# slice_v6_zp.net
KiCad netlist of a schematic drawn in EAGLE
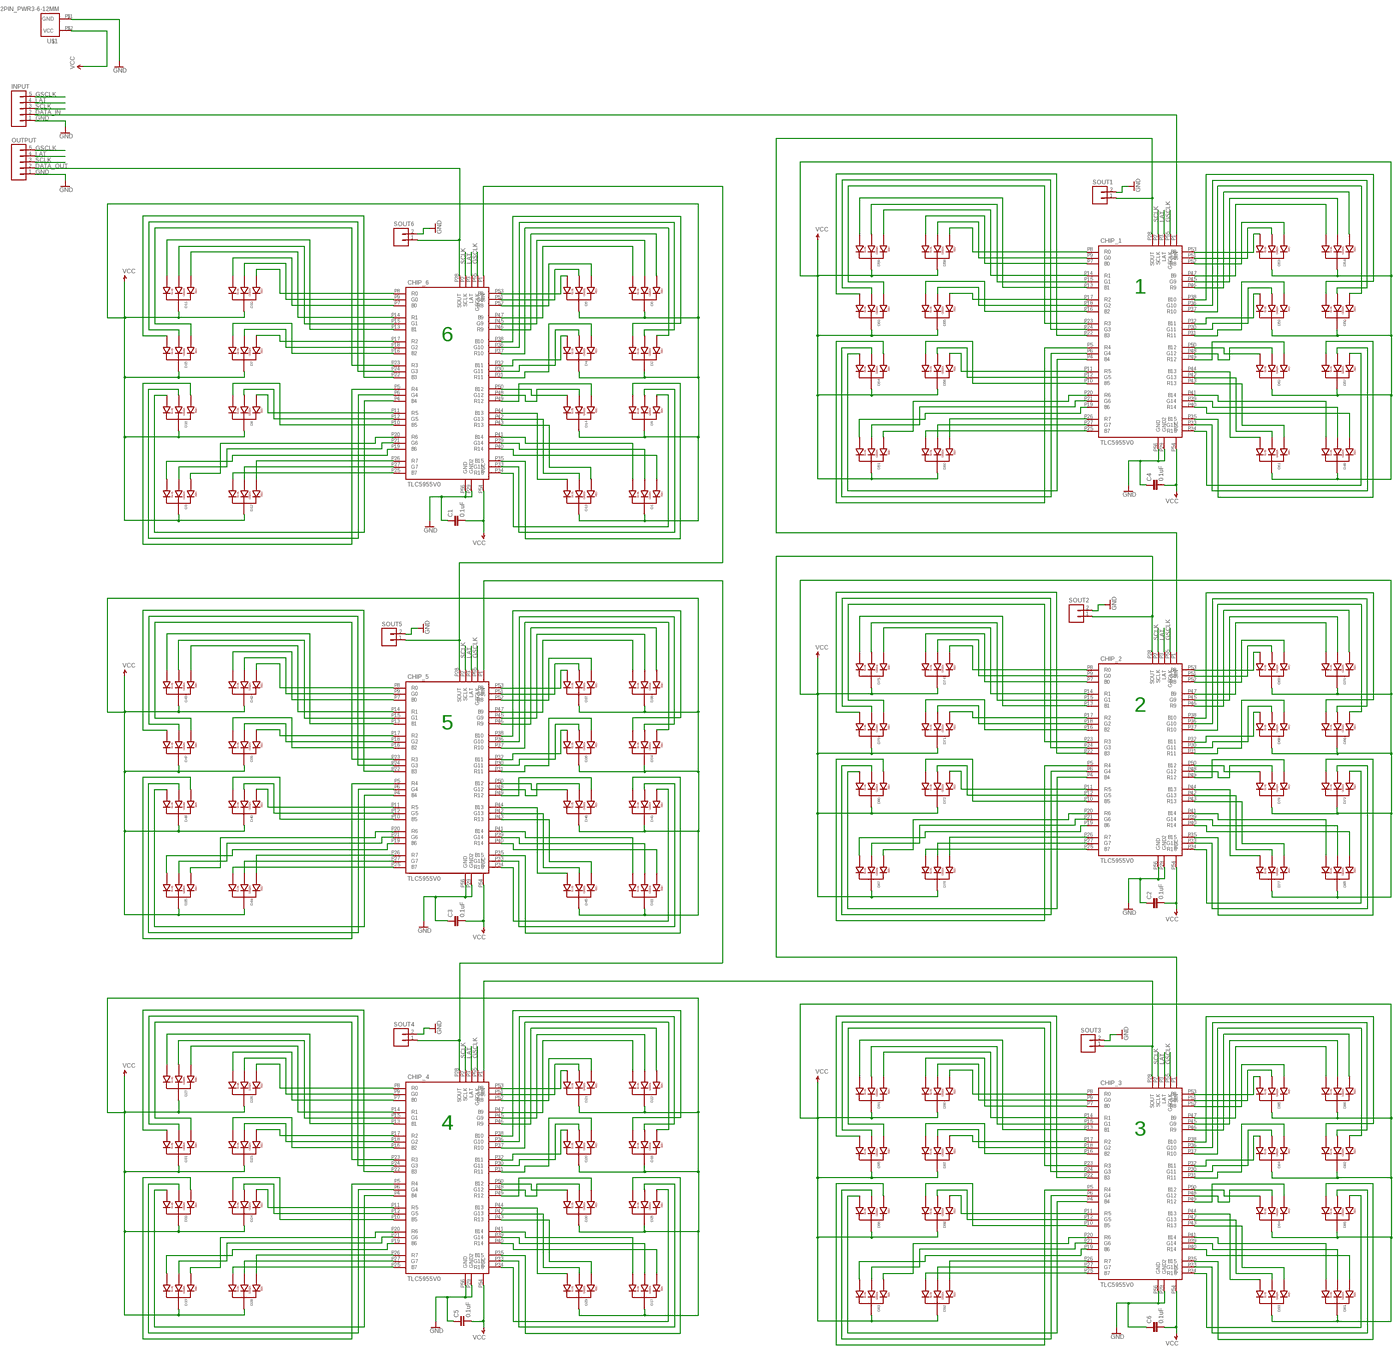
[diagram p0: schematic, sheet 1, overview]
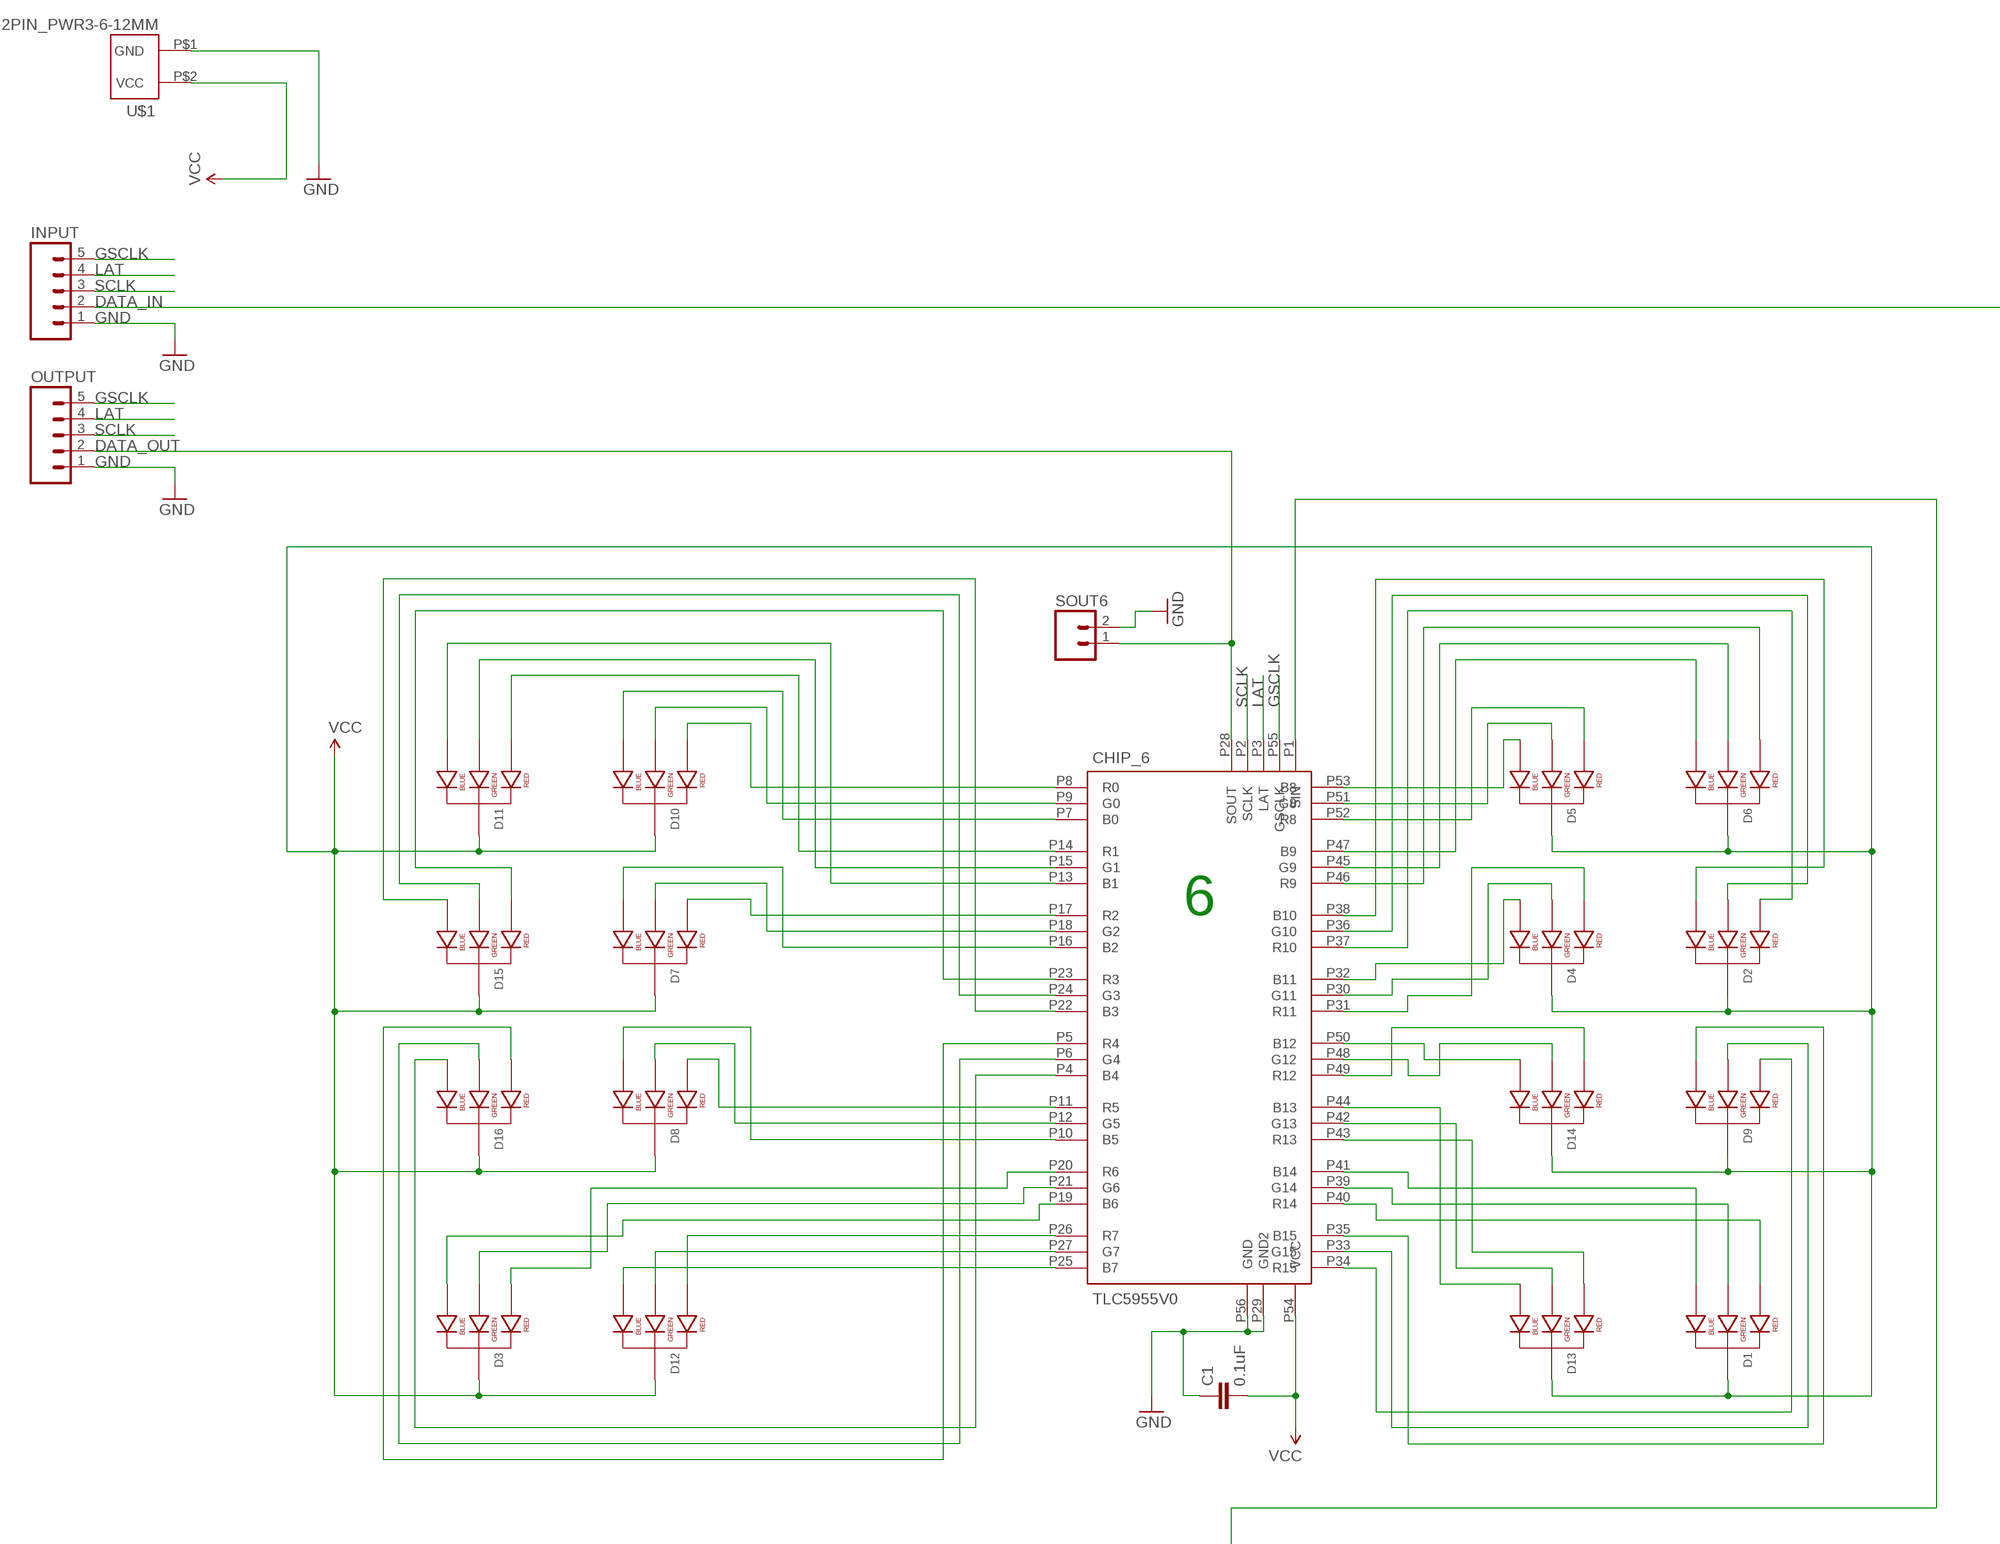
[diagram p1: schematic, sheet 1, part 1 of 4]
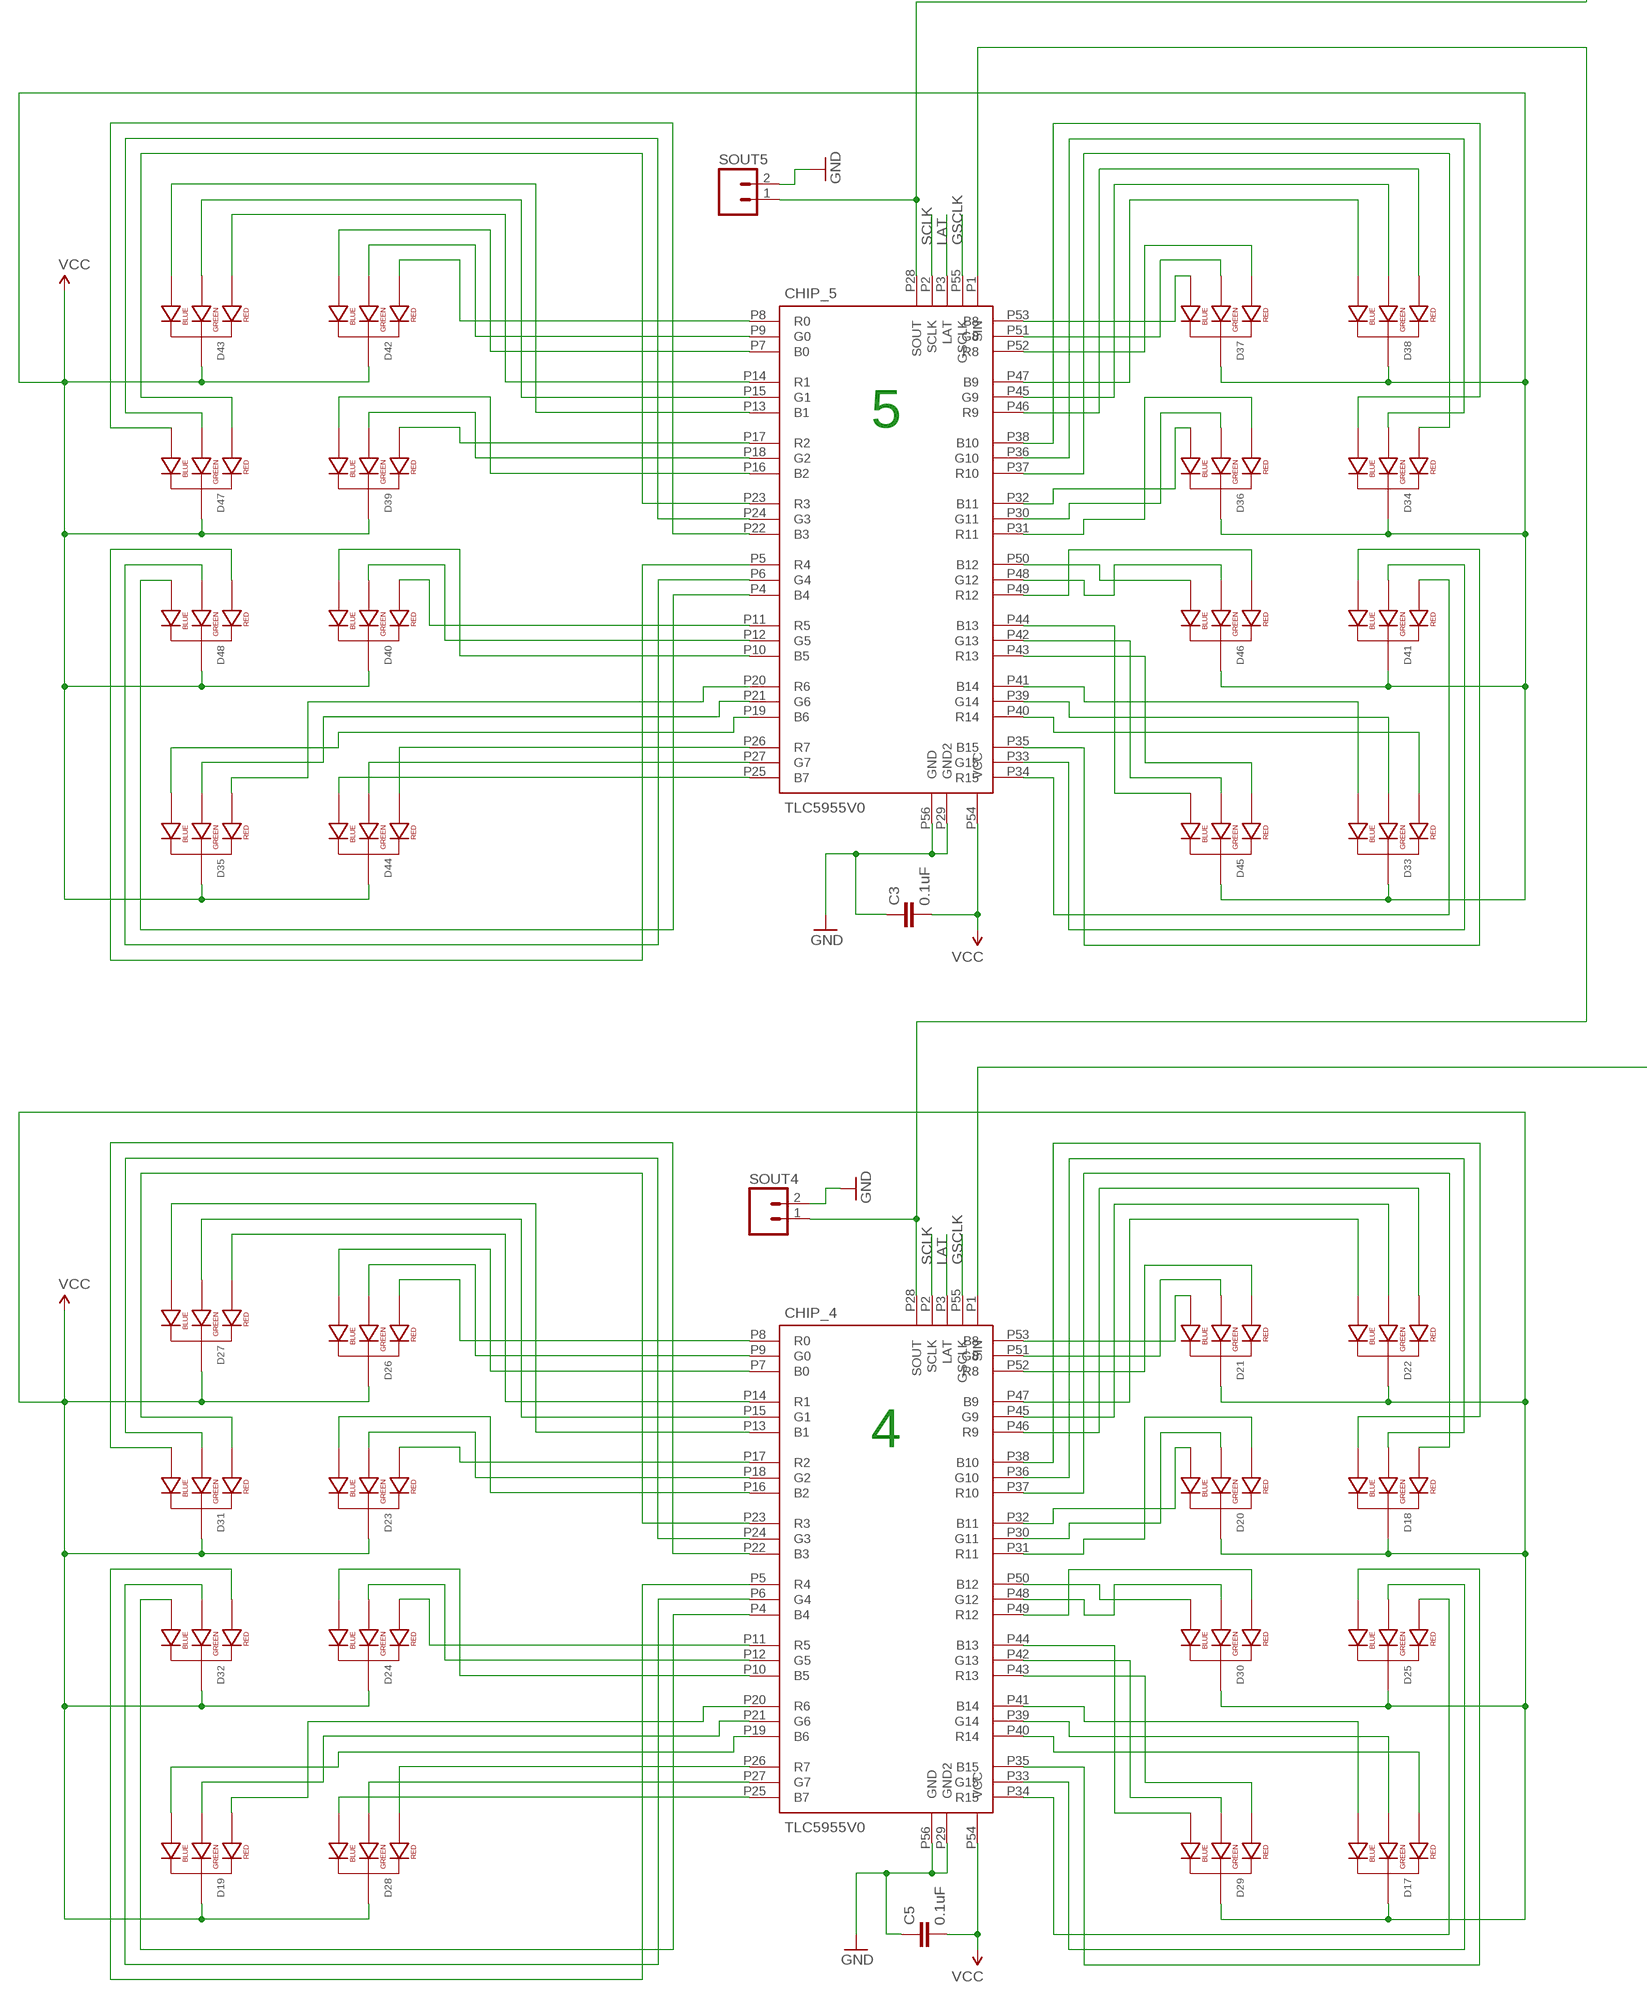
[diagram p2: schematic, sheet 1, part 2 of 4]
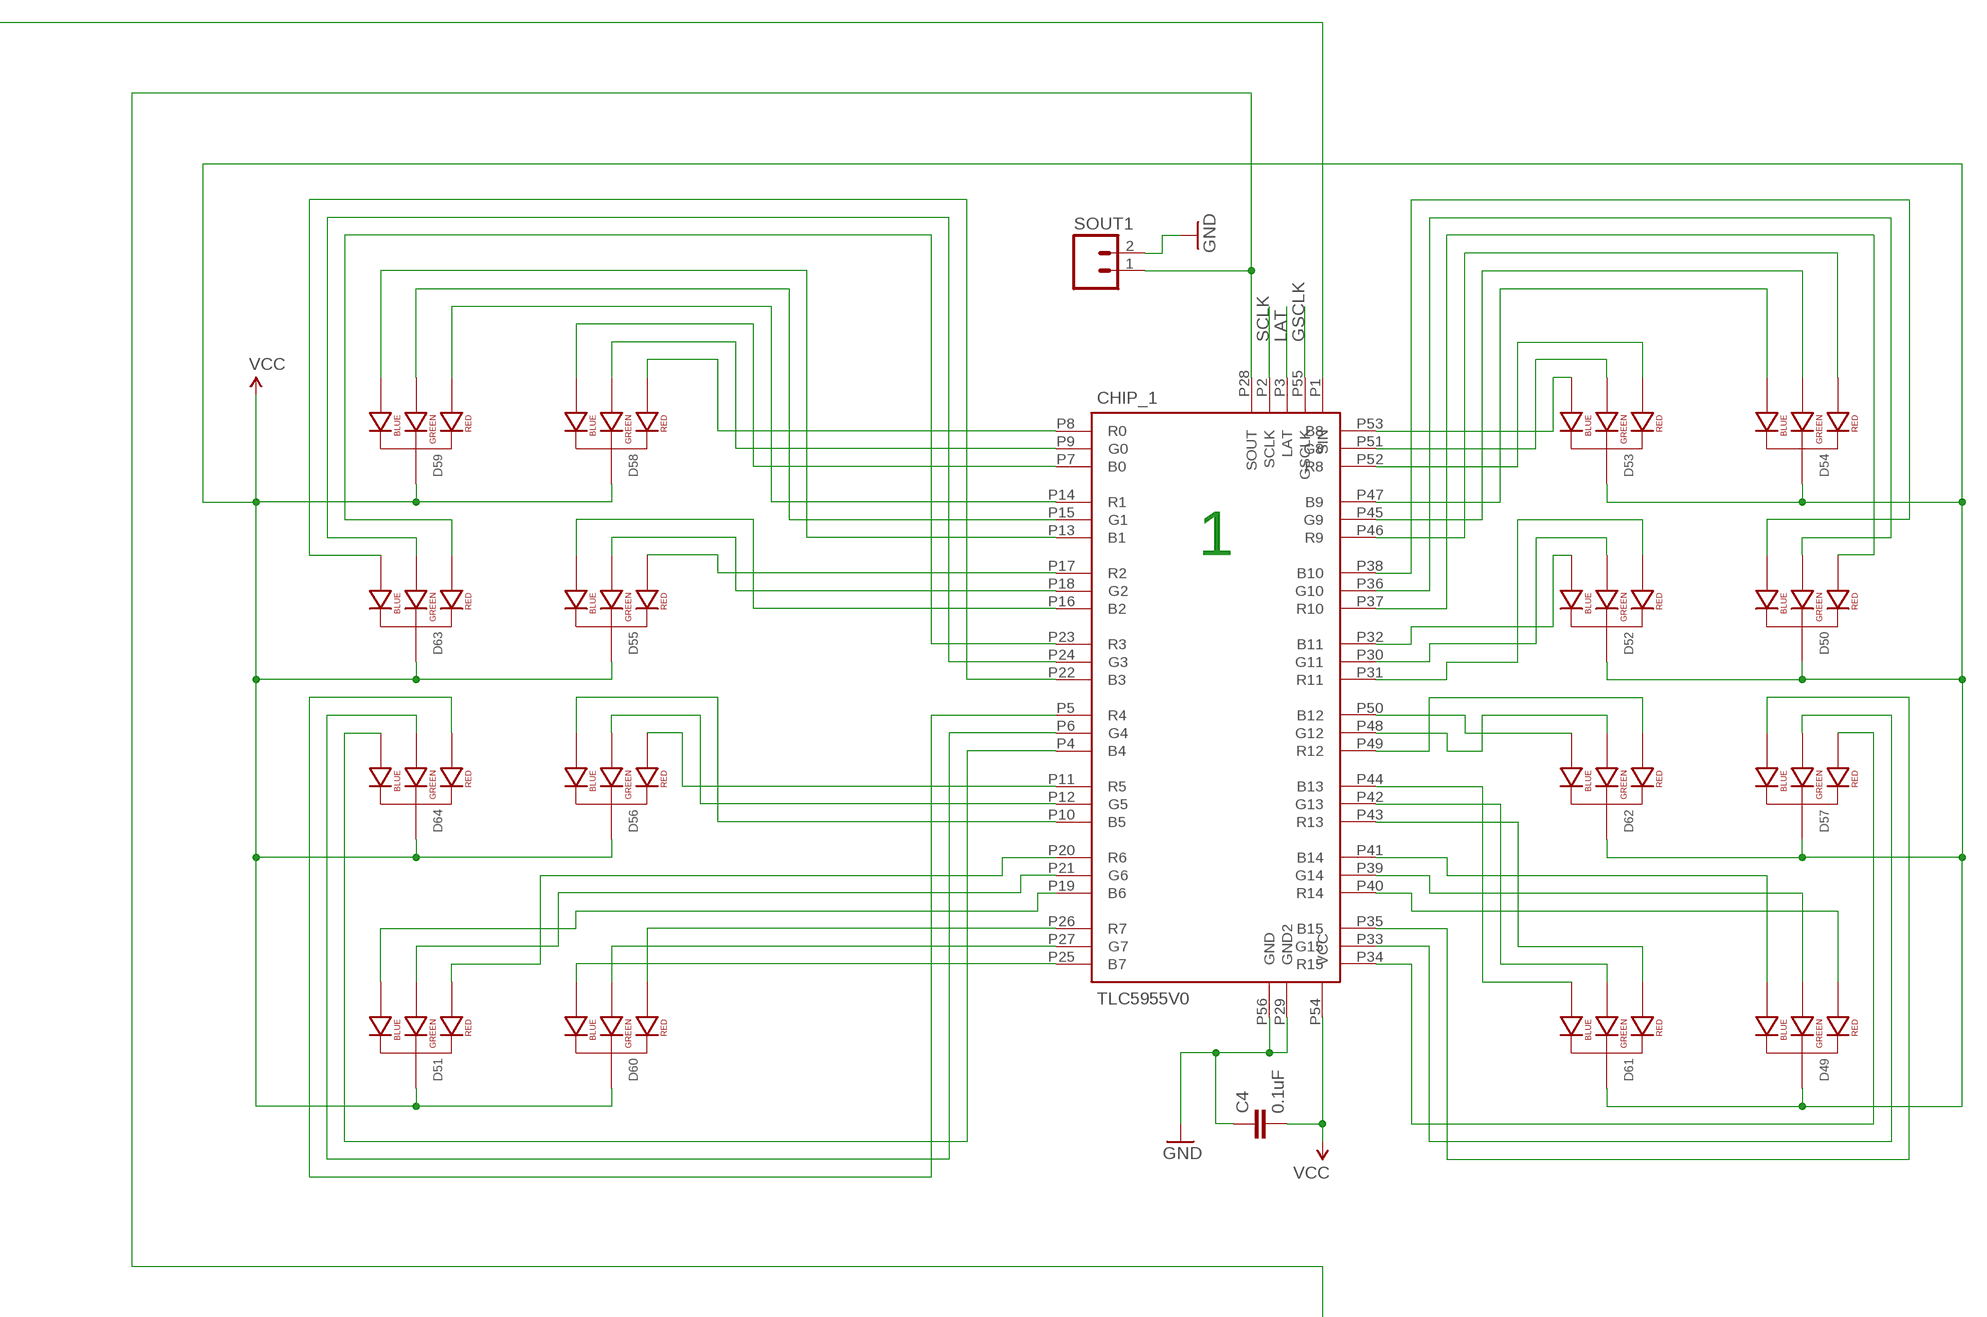
[diagram p3: schematic, sheet 1, part 3 of 4]
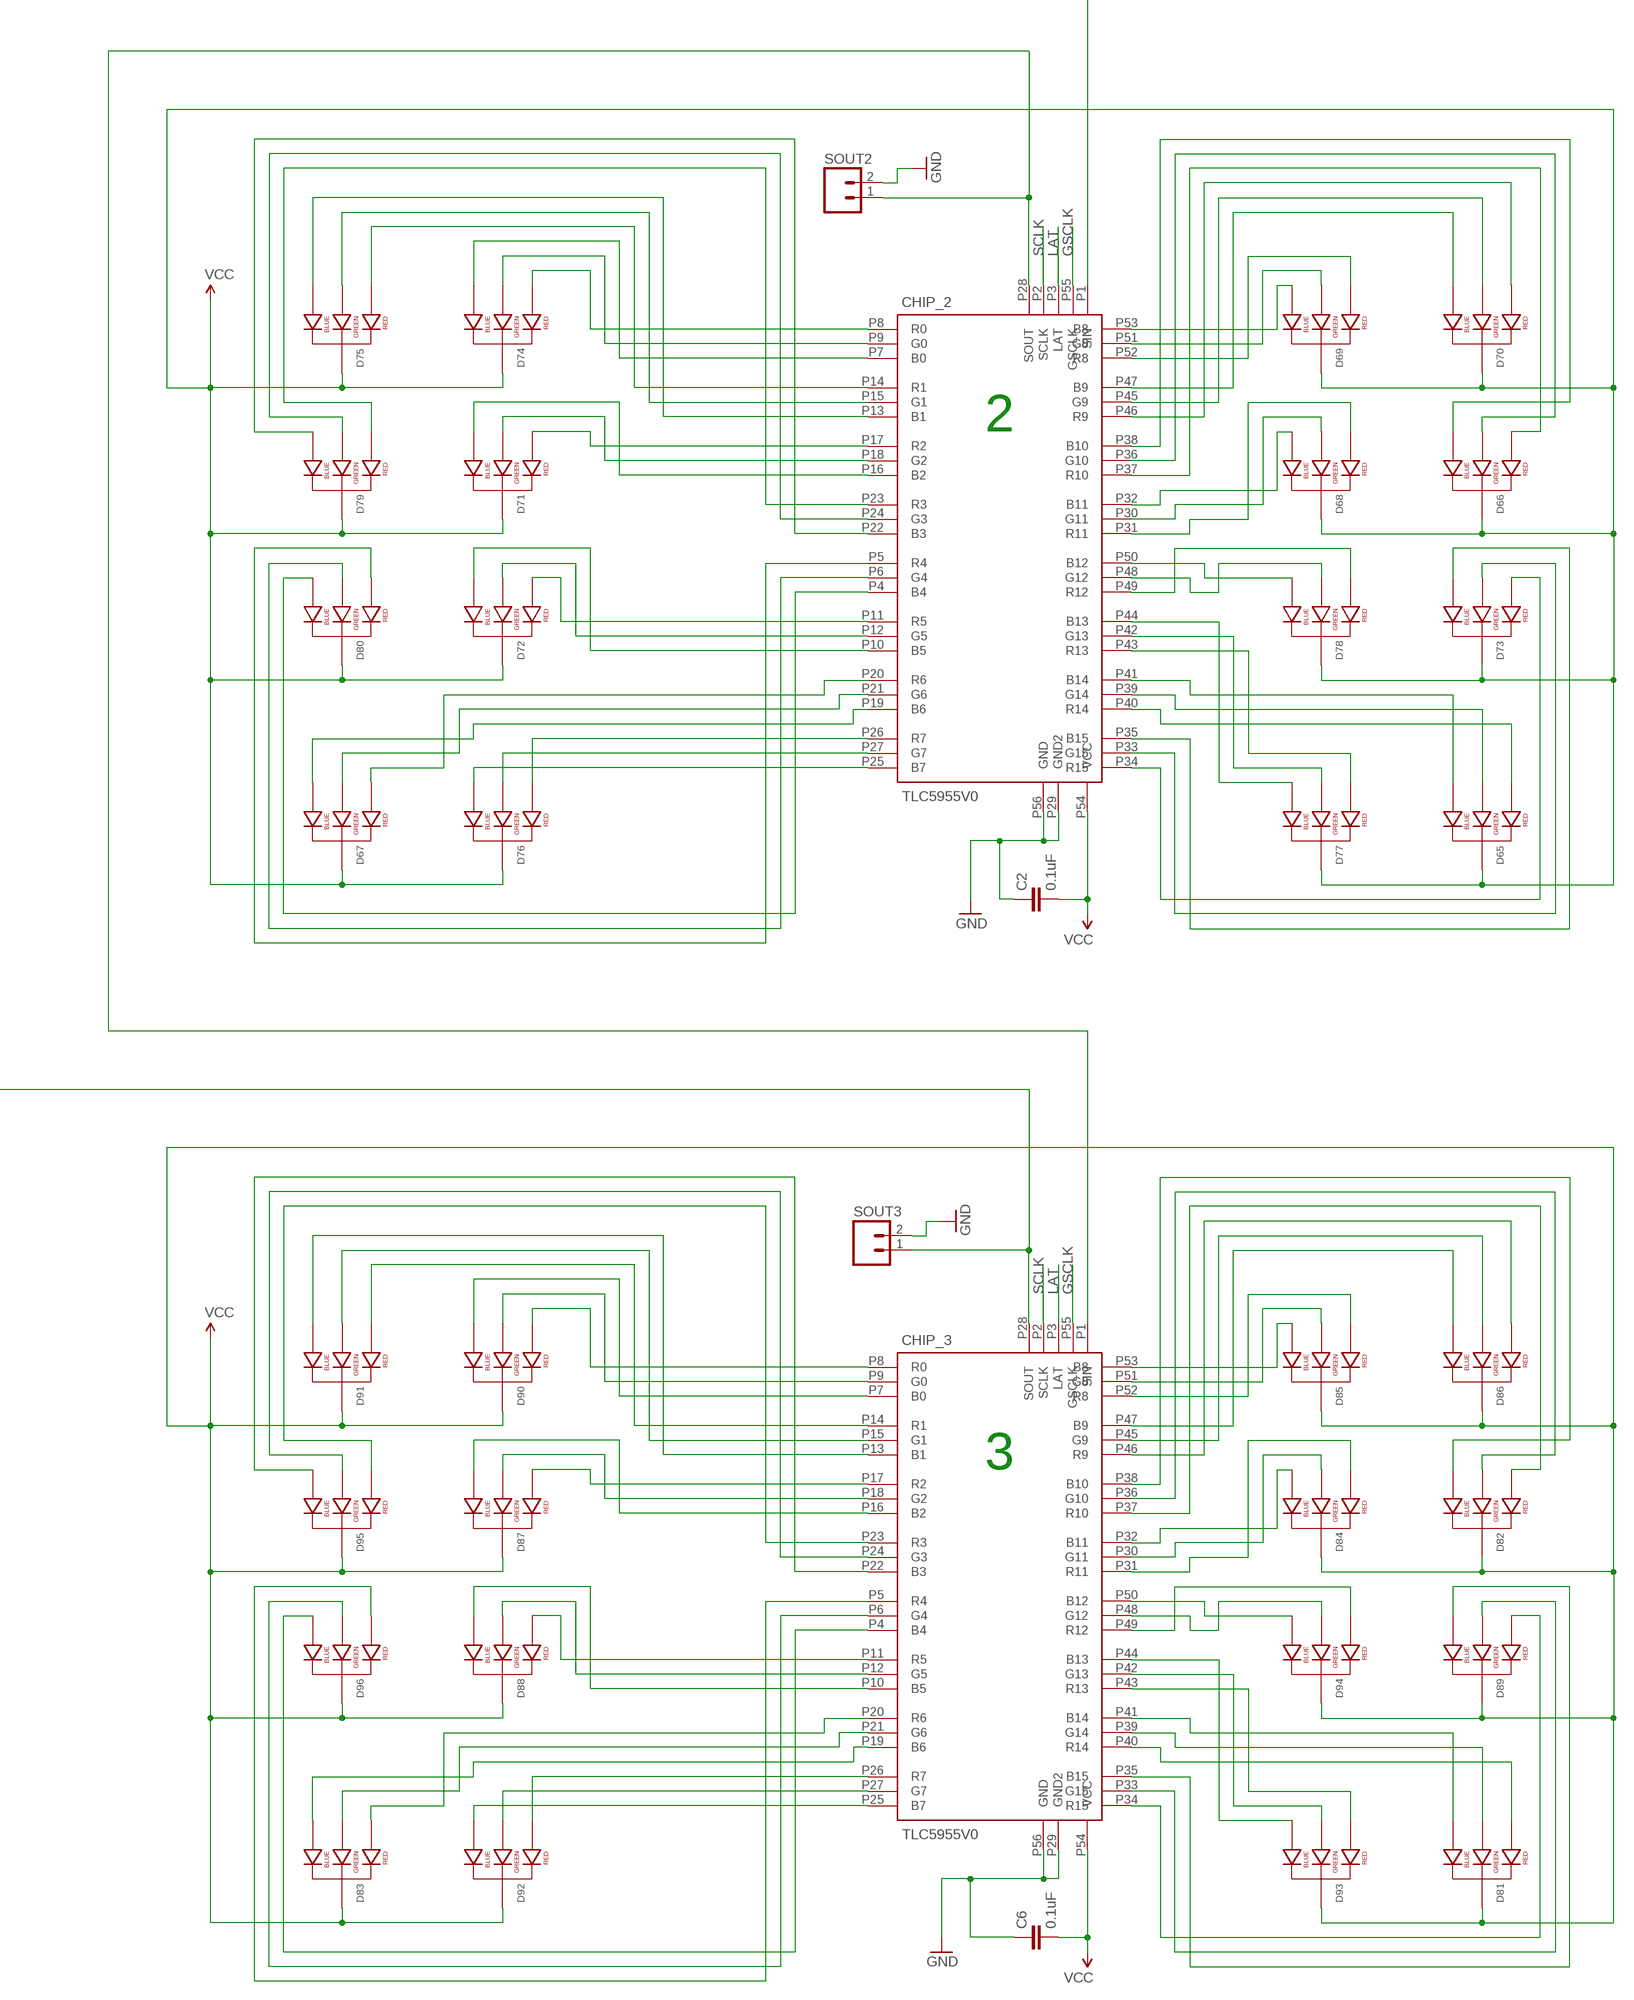
[diagram p4: schematic, sheet 1, part 4 of 4]

(export (version "E")
  (design (tool "Eeschema 10.0.6"))
  (components
    (comp (ref "C1")
      (value "0.1uF")
      (footprint "eagle-import:0603-CAP")
      (libsource (lib "eagle-import") (part "0.1UF-25V(+80/-20%)(0603)"))
    )
    (comp (ref "C2")
      (value "0.1uF")
      (footprint "eagle-import:0603-CAP")
      (libsource (lib "eagle-import") (part "0.1UF-25V(+80/-20%)(0603)"))
    )
    (comp (ref "C3")
      (value "0.1uF")
      (footprint "eagle-import:0603-CAP")
      (libsource (lib "eagle-import") (part "0.1UF-25V(+80/-20%)(0603)"))
    )
    (comp (ref "C4")
      (value "0.1uF")
      (footprint "eagle-import:0603-CAP")
      (libsource (lib "eagle-import") (part "0.1UF-25V(+80/-20%)(0603)"))
    )
    (comp (ref "C5")
      (value "0.1uF")
      (footprint "eagle-import:0603-CAP")
      (libsource (lib "eagle-import") (part "0.1UF-25V(+80/-20%)(0603)"))
    )
    (comp (ref "C6")
      (value "0.1uF")
      (footprint "eagle-import:0603-CAP")
      (libsource (lib "eagle-import") (part "0.1UF-25V(+80/-20%)(0603)"))
    )
    (comp (ref "CHIP_1")
      (value "TLC5955V0")
      (footprint "eagle-import:56-HTSSOP")
      (libsource (lib "eagle-import") (part "TLC5955V0"))
    )
    (comp (ref "CHIP_2")
      (value "TLC5955V0")
      (footprint "eagle-import:56-HTSSOP")
      (libsource (lib "eagle-import") (part "TLC5955V0"))
    )
    (comp (ref "CHIP_3")
      (value "TLC5955V0")
      (footprint "eagle-import:56-HTSSOP")
      (libsource (lib "eagle-import") (part "TLC5955V0"))
    )
    (comp (ref "CHIP_4")
      (value "TLC5955V0")
      (footprint "eagle-import:56-HTSSOP")
      (libsource (lib "eagle-import") (part "TLC5955V0"))
    )
    (comp (ref "CHIP_5")
      (value "TLC5955V0")
      (footprint "eagle-import:56-HTSSOP")
      (libsource (lib "eagle-import") (part "TLC5955V0"))
    )
    (comp (ref "CHIP_6")
      (value "TLC5955V0")
      (footprint "eagle-import:56-HTSSOP")
      (libsource (lib "eagle-import") (part "TLC5955V0"))
    )
    (comp (ref "D1")
      (value "LED-RGB-CC-THRUCLEAR")
      (footprint "eagle-import:LED-RGB-THRU")
      (libsource (lib "eagle-import") (part "LED-RGB-CC-THRUCLEAR"))
    )
    (comp (ref "D2")
      (value "LED-RGB-CC-THRUCLEAR")
      (footprint "eagle-import:LED-RGB-THRU")
      (libsource (lib "eagle-import") (part "LED-RGB-CC-THRUCLEAR"))
    )
    (comp (ref "D3")
      (value "LED-RGB-CC-THRUCLEAR")
      (footprint "eagle-import:LED-RGB-THRU")
      (libsource (lib "eagle-import") (part "LED-RGB-CC-THRUCLEAR"))
    )
    (comp (ref "D4")
      (value "LED-RGB-CC-THRUCLEAR")
      (footprint "eagle-import:LED-RGB-THRU")
      (libsource (lib "eagle-import") (part "LED-RGB-CC-THRUCLEAR"))
    )
    (comp (ref "D5")
      (value "LED-RGB-CC-THRUCLEAR")
      (footprint "eagle-import:LED-RGB-THRU")
      (libsource (lib "eagle-import") (part "LED-RGB-CC-THRUCLEAR"))
    )
    (comp (ref "D6")
      (value "LED-RGB-CC-THRUCLEAR")
      (footprint "eagle-import:LED-RGB-THRU")
      (libsource (lib "eagle-import") (part "LED-RGB-CC-THRUCLEAR"))
    )
    (comp (ref "D7")
      (value "LED-RGB-CC-THRUCLEAR")
      (footprint "eagle-import:LED-RGB-THRU")
      (libsource (lib "eagle-import") (part "LED-RGB-CC-THRUCLEAR"))
    )
    (comp (ref "D8")
      (value "LED-RGB-CC-THRUCLEAR")
      (footprint "eagle-import:LED-RGB-THRU")
      (libsource (lib "eagle-import") (part "LED-RGB-CC-THRUCLEAR"))
    )
    (comp (ref "D9")
      (value "LED-RGB-CC-THRUCLEAR")
      (footprint "eagle-import:LED-RGB-THRU")
      (libsource (lib "eagle-import") (part "LED-RGB-CC-THRUCLEAR"))
    )
    (comp (ref "D10")
      (value "LED-RGB-CC-THRUCLEAR")
      (footprint "eagle-import:LED-RGB-THRU")
      (libsource (lib "eagle-import") (part "LED-RGB-CC-THRUCLEAR"))
    )
    (comp (ref "D11")
      (value "LED-RGB-CC-THRUDIFFUSE")
      (footprint "eagle-import:LED-RGB-THRU")
      (libsource (lib "eagle-import") (part "LED-RGB-CC-THRUCLEAR"))
    )
    (comp (ref "D12")
      (value "LED-RGB-CC-THRUCLEAR")
      (footprint "eagle-import:LED-RGB-THRU")
      (libsource (lib "eagle-import") (part "LED-RGB-CC-THRUCLEAR"))
    )
    (comp (ref "D13")
      (value "LED-RGB-CC-THRUCLEAR")
      (footprint "eagle-import:LED-RGB-THRU")
      (libsource (lib "eagle-import") (part "LED-RGB-CC-THRUCLEAR"))
    )
    (comp (ref "D14")
      (value "LED-RGB-CC-THRUCLEAR")
      (footprint "eagle-import:LED-RGB-THRU")
      (libsource (lib "eagle-import") (part "LED-RGB-CC-THRUCLEAR"))
    )
    (comp (ref "D15")
      (value "LED-RGB-CC-THRUCLEAR")
      (footprint "eagle-import:LED-RGB-THRU")
      (libsource (lib "eagle-import") (part "LED-RGB-CC-THRUCLEAR"))
    )
    (comp (ref "D16")
      (value "LED-RGB-CC-THRUCLEAR")
      (footprint "eagle-import:LED-RGB-THRU")
      (libsource (lib "eagle-import") (part "LED-RGB-CC-THRUCLEAR"))
    )
    (comp (ref "D17")
      (value "LED-RGB-CC-THRUCLEAR")
      (footprint "eagle-import:LED-RGB-THRU")
      (libsource (lib "eagle-import") (part "LED-RGB-CC-THRUCLEAR"))
    )
    (comp (ref "D18")
      (value "LED-RGB-CC-THRUCLEAR")
      (footprint "eagle-import:LED-RGB-THRU")
      (libsource (lib "eagle-import") (part "LED-RGB-CC-THRUCLEAR"))
    )
    (comp (ref "D19")
      (value "LED-RGB-CC-THRUCLEAR")
      (footprint "eagle-import:LED-RGB-THRU")
      (libsource (lib "eagle-import") (part "LED-RGB-CC-THRUCLEAR"))
    )
    (comp (ref "D20")
      (value "LED-RGB-CC-THRUCLEAR")
      (footprint "eagle-import:LED-RGB-THRU")
      (libsource (lib "eagle-import") (part "LED-RGB-CC-THRUCLEAR"))
    )
    (comp (ref "D21")
      (value "LED-RGB-CC-THRUCLEAR")
      (footprint "eagle-import:LED-RGB-THRU")
      (libsource (lib "eagle-import") (part "LED-RGB-CC-THRUCLEAR"))
    )
    (comp (ref "D22")
      (value "LED-RGB-CC-THRUCLEAR")
      (footprint "eagle-import:LED-RGB-THRU")
      (libsource (lib "eagle-import") (part "LED-RGB-CC-THRUCLEAR"))
    )
    (comp (ref "D23")
      (value "LED-RGB-CC-THRUCLEAR")
      (footprint "eagle-import:LED-RGB-THRU")
      (libsource (lib "eagle-import") (part "LED-RGB-CC-THRUCLEAR"))
    )
    (comp (ref "D24")
      (value "LED-RGB-CC-THRUCLEAR")
      (footprint "eagle-import:LED-RGB-THRU")
      (libsource (lib "eagle-import") (part "LED-RGB-CC-THRUCLEAR"))
    )
    (comp (ref "D25")
      (value "LED-RGB-CC-THRUCLEAR")
      (footprint "eagle-import:LED-RGB-THRU")
      (libsource (lib "eagle-import") (part "LED-RGB-CC-THRUCLEAR"))
    )
    (comp (ref "D26")
      (value "LED-RGB-CC-THRUCLEAR")
      (footprint "eagle-import:LED-RGB-THRU")
      (libsource (lib "eagle-import") (part "LED-RGB-CC-THRUCLEAR"))
    )
    (comp (ref "D27")
      (value "LED-RGB-CC-THRUCLEAR")
      (footprint "eagle-import:LED-RGB-THRU")
      (libsource (lib "eagle-import") (part "LED-RGB-CC-THRUCLEAR"))
    )
    (comp (ref "D28")
      (value "LED-RGB-CC-THRUCLEAR")
      (footprint "eagle-import:LED-RGB-THRU")
      (libsource (lib "eagle-import") (part "LED-RGB-CC-THRUCLEAR"))
    )
    (comp (ref "D29")
      (value "LED-RGB-CC-THRUCLEAR")
      (footprint "eagle-import:LED-RGB-THRU")
      (libsource (lib "eagle-import") (part "LED-RGB-CC-THRUCLEAR"))
    )
    (comp (ref "D30")
      (value "LED-RGB-CC-THRUCLEAR")
      (footprint "eagle-import:LED-RGB-THRU")
      (libsource (lib "eagle-import") (part "LED-RGB-CC-THRUCLEAR"))
    )
    (comp (ref "D31")
      (value "LED-RGB-CC-THRUCLEAR")
      (footprint "eagle-import:LED-RGB-THRU")
      (libsource (lib "eagle-import") (part "LED-RGB-CC-THRUCLEAR"))
    )
    (comp (ref "D32")
      (value "LED-RGB-CC-THRUCLEAR")
      (footprint "eagle-import:LED-RGB-THRU")
      (libsource (lib "eagle-import") (part "LED-RGB-CC-THRUCLEAR"))
    )
    (comp (ref "D33")
      (value "LED-RGB-CC-THRUCLEAR")
      (footprint "eagle-import:LED-RGB-THRU")
      (libsource (lib "eagle-import") (part "LED-RGB-CC-THRUCLEAR"))
    )
    (comp (ref "D34")
      (value "LED-RGB-CC-THRUCLEAR")
      (footprint "eagle-import:LED-RGB-THRU")
      (libsource (lib "eagle-import") (part "LED-RGB-CC-THRUCLEAR"))
    )
    (comp (ref "D35")
      (value "1")
      (footprint "eagle-import:LED-RGB-THRU")
      (libsource (lib "eagle-import") (part "LED-RGB-CC-THRUCLEAR"))
    )
    (comp (ref "D36")
      (value "LED-RGB-CC-THRUCLEAR")
      (footprint "eagle-import:LED-RGB-THRU")
      (libsource (lib "eagle-import") (part "LED-RGB-CC-THRUCLEAR"))
    )
    (comp (ref "D37")
      (value "LED-RGB-CC-THRUCLEAR")
      (footprint "eagle-import:LED-RGB-THRU")
      (libsource (lib "eagle-import") (part "LED-RGB-CC-THRUCLEAR"))
    )
    (comp (ref "D38")
      (value "LED-RGB-CC-THRUCLEAR")
      (footprint "eagle-import:LED-RGB-THRU")
      (libsource (lib "eagle-import") (part "LED-RGB-CC-THRUCLEAR"))
    )
    (comp (ref "D39")
      (value "LED-RGB-CC-THRUCLEAR")
      (footprint "eagle-import:LED-RGB-THRU")
      (libsource (lib "eagle-import") (part "LED-RGB-CC-THRUCLEAR"))
    )
    (comp (ref "D40")
      (value "LED-RGB-CC-THRUCLEAR")
      (footprint "eagle-import:LED-RGB-THRU")
      (libsource (lib "eagle-import") (part "LED-RGB-CC-THRUCLEAR"))
    )
    (comp (ref "D41")
      (value "LED-RGB-CC-THRUCLEAR")
      (footprint "eagle-import:LED-RGB-THRU")
      (libsource (lib "eagle-import") (part "LED-RGB-CC-THRUCLEAR"))
    )
    (comp (ref "D42")
      (value "LED-RGB-CC-THRUCLEAR")
      (footprint "eagle-import:LED-RGB-THRU")
      (libsource (lib "eagle-import") (part "LED-RGB-CC-THRUCLEAR"))
    )
    (comp (ref "D43")
      (value "LED-RGB-CC-THRUCLEAR")
      (footprint "eagle-import:LED-RGB-THRU")
      (libsource (lib "eagle-import") (part "LED-RGB-CC-THRUCLEAR"))
    )
    (comp (ref "D44")
      (value "LED-RGB-CC-THRUCLEAR")
      (footprint "eagle-import:LED-RGB-THRU")
      (libsource (lib "eagle-import") (part "LED-RGB-CC-THRUCLEAR"))
    )
    (comp (ref "D45")
      (value "LED-RGB-CC-THRUCLEAR")
      (footprint "eagle-import:LED-RGB-THRU")
      (libsource (lib "eagle-import") (part "LED-RGB-CC-THRUCLEAR"))
    )
    (comp (ref "D46")
      (value "LED-RGB-CC-THRUCLEAR")
      (footprint "eagle-import:LED-RGB-THRU")
      (libsource (lib "eagle-import") (part "LED-RGB-CC-THRUCLEAR"))
    )
    (comp (ref "D47")
      (value "LED-RGB-CC-THRUCLEAR")
      (footprint "eagle-import:LED-RGB-THRU")
      (libsource (lib "eagle-import") (part "LED-RGB-CC-THRUCLEAR"))
    )
    (comp (ref "D48")
      (value "LED-RGB-CC-THRUCLEAR")
      (footprint "eagle-import:LED-RGB-THRU")
      (libsource (lib "eagle-import") (part "LED-RGB-CC-THRUCLEAR"))
    )
    (comp (ref "D49")
      (value "LED-RGB-CC-THRUCLEAR")
      (footprint "eagle-import:LED-RGB-THRU")
      (libsource (lib "eagle-import") (part "LED-RGB-CC-THRUCLEAR"))
    )
    (comp (ref "D50")
      (value "LED-RGB-CC-THRUCLEAR")
      (footprint "eagle-import:LED-RGB-THRU")
      (libsource (lib "eagle-import") (part "LED-RGB-CC-THRUCLEAR"))
    )
    (comp (ref "D51")
      (value "LED-RGB-CC-THRUCLEAR")
      (footprint "eagle-import:LED-RGB-THRU")
      (libsource (lib "eagle-import") (part "LED-RGB-CC-THRUCLEAR"))
    )
    (comp (ref "D52")
      (value "LED-RGB-CC-THRUCLEAR")
      (footprint "eagle-import:LED-RGB-THRU")
      (libsource (lib "eagle-import") (part "LED-RGB-CC-THRUCLEAR"))
    )
    (comp (ref "D53")
      (value "LED-RGB-CC-THRUCLEAR")
      (footprint "eagle-import:LED-RGB-THRU")
      (libsource (lib "eagle-import") (part "LED-RGB-CC-THRUCLEAR"))
    )
    (comp (ref "D54")
      (value "LED-RGB-CC-THRUCLEAR")
      (footprint "eagle-import:LED-RGB-THRU")
      (libsource (lib "eagle-import") (part "LED-RGB-CC-THRUCLEAR"))
    )
    (comp (ref "D55")
      (value "LED-RGB-CC-THRUCLEAR")
      (footprint "eagle-import:LED-RGB-THRU")
      (libsource (lib "eagle-import") (part "LED-RGB-CC-THRUCLEAR"))
    )
    (comp (ref "D56")
      (value "LED-RGB-CC-THRUCLEAR")
      (footprint "eagle-import:LED-RGB-THRU")
      (libsource (lib "eagle-import") (part "LED-RGB-CC-THRUCLEAR"))
    )
    (comp (ref "D57")
      (value "LED-RGB-CC-THRUCLEAR")
      (footprint "eagle-import:LED-RGB-THRU")
      (libsource (lib "eagle-import") (part "LED-RGB-CC-THRUCLEAR"))
    )
    (comp (ref "D58")
      (value "LED-RGB-CC-THRUCLEAR")
      (footprint "eagle-import:LED-RGB-THRU")
      (libsource (lib "eagle-import") (part "LED-RGB-CC-THRUCLEAR"))
    )
    (comp (ref "D59")
      (value "LED-RGB-CC-THRUCLEAR")
      (footprint "eagle-import:LED-RGB-THRU")
      (libsource (lib "eagle-import") (part "LED-RGB-CC-THRUCLEAR"))
    )
    (comp (ref "D60")
      (value "LED-RGB-CC-THRUCLEAR")
      (footprint "eagle-import:LED-RGB-THRU")
      (libsource (lib "eagle-import") (part "LED-RGB-CC-THRUCLEAR"))
    )
    (comp (ref "D61")
      (value "LED-RGB-CC-THRUCLEAR")
      (footprint "eagle-import:LED-RGB-THRU")
      (libsource (lib "eagle-import") (part "LED-RGB-CC-THRUCLEAR"))
    )
    (comp (ref "D62")
      (value "LED-RGB-CC-THRUCLEAR")
      (footprint "eagle-import:LED-RGB-THRU")
      (libsource (lib "eagle-import") (part "LED-RGB-CC-THRUCLEAR"))
    )
    (comp (ref "D63")
      (value "LED-RGB-CC-THRUCLEAR")
      (footprint "eagle-import:LED-RGB-THRU")
      (libsource (lib "eagle-import") (part "LED-RGB-CC-THRUCLEAR"))
    )
    (comp (ref "D64")
      (value "LED-RGB-CC-THRUCLEAR")
      (footprint "eagle-import:LED-RGB-THRU")
      (libsource (lib "eagle-import") (part "LED-RGB-CC-THRUCLEAR"))
    )
    (comp (ref "D65")
      (value "LED-RGB-CC-THRUCLEAR")
      (footprint "eagle-import:LED-RGB-THRU")
      (libsource (lib "eagle-import") (part "LED-RGB-CC-THRUCLEAR"))
    )
    (comp (ref "D66")
      (value "LED-RGB-CC-THRUCLEAR")
      (footprint "eagle-import:LED-RGB-THRU")
      (libsource (lib "eagle-import") (part "LED-RGB-CC-THRUCLEAR"))
    )
    (comp (ref "D67")
      (value "LED-RGB-CC-THRUCLEAR")
      (footprint "eagle-import:LED-RGB-THRU")
      (libsource (lib "eagle-import") (part "LED-RGB-CC-THRUCLEAR"))
    )
    (comp (ref "D68")
      (value "LED-RGB-CC-THRUCLEAR")
      (footprint "eagle-import:LED-RGB-THRU")
      (libsource (lib "eagle-import") (part "LED-RGB-CC-THRUCLEAR"))
    )
    (comp (ref "D69")
      (value "LED-RGB-CC-THRUCLEAR")
      (footprint "eagle-import:LED-RGB-THRU")
      (libsource (lib "eagle-import") (part "LED-RGB-CC-THRUCLEAR"))
    )
    (comp (ref "D70")
      (value "LED-RGB-CC-THRUCLEAR")
      (footprint "eagle-import:LED-RGB-THRU")
      (libsource (lib "eagle-import") (part "LED-RGB-CC-THRUCLEAR"))
    )
    (comp (ref "D71")
      (value "LED-RGB-CC-THRUCLEAR")
      (footprint "eagle-import:LED-RGB-THRU")
      (libsource (lib "eagle-import") (part "LED-RGB-CC-THRUCLEAR"))
    )
    (comp (ref "D72")
      (value "LED-RGB-CC-THRUCLEAR")
      (footprint "eagle-import:LED-RGB-THRU")
      (libsource (lib "eagle-import") (part "LED-RGB-CC-THRUCLEAR"))
    )
    (comp (ref "D73")
      (value "LED-RGB-CC-THRUCLEAR")
      (footprint "eagle-import:LED-RGB-THRU")
      (libsource (lib "eagle-import") (part "LED-RGB-CC-THRUCLEAR"))
    )
    (comp (ref "D74")
      (value "LED-RGB-CC-THRUCLEAR")
      (footprint "eagle-import:LED-RGB-THRU")
      (libsource (lib "eagle-import") (part "LED-RGB-CC-THRUCLEAR"))
    )
    (comp (ref "D75")
      (value "LED-RGB-CC-THRUCLEAR")
      (footprint "eagle-import:LED-RGB-THRU")
      (libsource (lib "eagle-import") (part "LED-RGB-CC-THRUCLEAR"))
    )
    (comp (ref "D76")
      (value "LED-RGB-CC-THRUCLEAR")
      (footprint "eagle-import:LED-RGB-THRU")
      (libsource (lib "eagle-import") (part "LED-RGB-CC-THRUCLEAR"))
    )
    (comp (ref "D77")
      (value "LED-RGB-CC-THRUCLEAR")
      (footprint "eagle-import:LED-RGB-THRU")
      (libsource (lib "eagle-import") (part "LED-RGB-CC-THRUCLEAR"))
    )
    (comp (ref "D78")
      (value "LED-RGB-CC-THRUCLEAR")
      (footprint "eagle-import:LED-RGB-THRU")
      (libsource (lib "eagle-import") (part "LED-RGB-CC-THRUCLEAR"))
    )
    (comp (ref "D79")
      (value "LED-RGB-CC-THRUCLEAR")
      (footprint "eagle-import:LED-RGB-THRU")
      (libsource (lib "eagle-import") (part "LED-RGB-CC-THRUCLEAR"))
    )
    (comp (ref "D80")
      (value "LED-RGB-CC-THRUCLEAR")
      (footprint "eagle-import:LED-RGB-THRU")
      (libsource (lib "eagle-import") (part "LED-RGB-CC-THRUCLEAR"))
    )
    (comp (ref "D81")
      (value "LED-RGB-CC-THRUCLEAR")
      (footprint "eagle-import:LED-RGB-THRU")
      (libsource (lib "eagle-import") (part "LED-RGB-CC-THRUCLEAR"))
    )
    (comp (ref "D82")
      (value "LED-RGB-CC-THRUCLEAR")
      (footprint "eagle-import:LED-RGB-THRU")
      (libsource (lib "eagle-import") (part "LED-RGB-CC-THRUCLEAR"))
    )
    (comp (ref "D83")
      (value "LED-RGB-CC-THRUCLEAR")
      (footprint "eagle-import:LED-RGB-THRU")
      (libsource (lib "eagle-import") (part "LED-RGB-CC-THRUCLEAR"))
    )
    (comp (ref "D84")
      (value "LED-RGB-CC-THRUCLEAR")
      (footprint "eagle-import:LED-RGB-THRU")
      (libsource (lib "eagle-import") (part "LED-RGB-CC-THRUCLEAR"))
    )
    (comp (ref "D85")
      (value "LED-RGB-CC-THRUCLEAR")
      (footprint "eagle-import:LED-RGB-THRU")
      (libsource (lib "eagle-import") (part "LED-RGB-CC-THRUCLEAR"))
    )
    (comp (ref "D86")
      (value "LED-RGB-CC-THRUCLEAR")
      (footprint "eagle-import:LED-RGB-THRU")
      (libsource (lib "eagle-import") (part "LED-RGB-CC-THRUCLEAR"))
    )
    (comp (ref "D87")
      (value "LED-RGB-CC-THRUCLEAR")
      (footprint "eagle-import:LED-RGB-THRU")
      (libsource (lib "eagle-import") (part "LED-RGB-CC-THRUCLEAR"))
    )
    (comp (ref "D88")
      (value "LED-RGB-CC-THRUCLEAR")
      (footprint "eagle-import:LED-RGB-THRU")
      (libsource (lib "eagle-import") (part "LED-RGB-CC-THRUCLEAR"))
    )
    (comp (ref "D89")
      (value "LED-RGB-CC-THRUCLEAR")
      (footprint "eagle-import:LED-RGB-THRU")
      (libsource (lib "eagle-import") (part "LED-RGB-CC-THRUCLEAR"))
    )
    (comp (ref "D90")
      (value "LED-RGB-CC-THRUCLEAR")
      (footprint "eagle-import:LED-RGB-THRU")
      (libsource (lib "eagle-import") (part "LED-RGB-CC-THRUCLEAR"))
    )
    (comp (ref "D91")
      (value "LED-RGB-CC-THRUCLEAR")
      (footprint "eagle-import:LED-RGB-THRU")
      (libsource (lib "eagle-import") (part "LED-RGB-CC-THRUCLEAR"))
    )
    (comp (ref "D92")
      (value "LED-RGB-CC-THRUCLEAR")
      (footprint "eagle-import:LED-RGB-THRU")
      (libsource (lib "eagle-import") (part "LED-RGB-CC-THRUCLEAR"))
    )
    (comp (ref "D93")
      (value "LED-RGB-CC-THRUCLEAR")
      (footprint "eagle-import:LED-RGB-THRU")
      (libsource (lib "eagle-import") (part "LED-RGB-CC-THRUCLEAR"))
    )
    (comp (ref "D94")
      (value "LED-RGB-CC-THRUCLEAR")
      (footprint "eagle-import:LED-RGB-THRU")
      (libsource (lib "eagle-import") (part "LED-RGB-CC-THRUCLEAR"))
    )
    (comp (ref "D95")
      (value "LED-RGB-CC-THRUCLEAR")
      (footprint "eagle-import:LED-RGB-THRU")
      (libsource (lib "eagle-import") (part "LED-RGB-CC-THRUCLEAR"))
    )
    (comp (ref "D96")
      (value "LED-RGB-CC-THRUCLEAR")
      (footprint "eagle-import:LED-RGB-THRU")
      (libsource (lib "eagle-import") (part "LED-RGB-CC-THRUCLEAR"))
    )
    (comp (ref "INPUT")
      (value "M05LOCK_LONGPADS")
      (footprint "eagle-import:1X05_LOCK_LONGPADS")
      (libsource (lib "eagle-import") (part "M05LOCK_LONGPADS"))
    )
    (comp (ref "OUTPUT")
      (value "M05LOCK_LONGPADS")
      (footprint "eagle-import:1X05_LOCK_LONGPADS")
      (libsource (lib "eagle-import") (part "M05LOCK_LONGPADS"))
    )
    (comp (ref "SOUT1")
      (value "M02LOCK")
      (footprint "eagle-import:1X02_LOCK")
      (libsource (lib "eagle-import") (part "M02LOCK"))
    )
    (comp (ref "SOUT2")
      (value "M02LOCK")
      (footprint "eagle-import:1X02_LOCK")
      (libsource (lib "eagle-import") (part "M02LOCK"))
    )
    (comp (ref "SOUT3")
      (value "M02LOCK")
      (footprint "eagle-import:1X02_LOCK")
      (libsource (lib "eagle-import") (part "M02LOCK"))
    )
    (comp (ref "SOUT4")
      (value "M02LOCK")
      (footprint "eagle-import:1X02_LOCK")
      (libsource (lib "eagle-import") (part "M02LOCK"))
    )
    (comp (ref "SOUT5")
      (value "M02LOCK")
      (footprint "eagle-import:1X02_LOCK")
      (libsource (lib "eagle-import") (part "M02LOCK"))
    )
    (comp (ref "SOUT6")
      (value "M02LOCK")
      (footprint "eagle-import:1X02_LOCK")
      (libsource (lib "eagle-import") (part "M02LOCK"))
    )
    (comp (ref "U$1")
      (value "2PIN_PWR3-6-12MM")
      (footprint "eagle-import:2PIN_HOLES_PWR")
      (libsource (lib "eagle-import") (part "2PIN_PWR3-6-12MM"))
    )
  )
  (nets
    (net (code "1") (name "/DATA_IN") (class "Default")
      (node (ref "CHIP_1") (pin "P1") (pinfunction "SIN_P1") (pintype "bidirectional"))
      (node (ref "INPUT") (pin "2") (pinfunction "2_2") (pintype "passive"))
    )
    (net (code "2") (name "/DATA_OUT") (class "Default")
      (node (ref "CHIP_6") (pin "P28") (pinfunction "SOUT_P28") (pintype "bidirectional"))
      (node (ref "OUTPUT") (pin "2") (pinfunction "2_2") (pintype "passive"))
      (node (ref "SOUT6") (pin "1") (pinfunction "1_1") (pintype "passive"))
    )
    (net (code "3") (name "/GSCLK") (class "Default")
      (node (ref "CHIP_1") (pin "P55") (pinfunction "GSCLK_P55") (pintype "bidirectional"))
      (node (ref "CHIP_2") (pin "P55") (pinfunction "GSCLK_P55") (pintype "bidirectional"))
      (node (ref "CHIP_3") (pin "P55") (pinfunction "GSCLK_P55") (pintype "bidirectional"))
      (node (ref "CHIP_4") (pin "P55") (pinfunction "GSCLK_P55") (pintype "bidirectional"))
      (node (ref "CHIP_5") (pin "P55") (pinfunction "GSCLK_P55") (pintype "bidirectional"))
      (node (ref "CHIP_6") (pin "P55") (pinfunction "GSCLK_P55") (pintype "bidirectional"))
      (node (ref "INPUT") (pin "5") (pinfunction "5_5") (pintype "passive"))
      (node (ref "OUTPUT") (pin "5") (pinfunction "5_5") (pintype "passive"))
    )
    (net (code "4") (name "/LAT") (class "Default")
      (node (ref "CHIP_1") (pin "P3") (pinfunction "LAT_P3") (pintype "bidirectional"))
      (node (ref "CHIP_2") (pin "P3") (pinfunction "LAT_P3") (pintype "bidirectional"))
      (node (ref "CHIP_3") (pin "P3") (pinfunction "LAT_P3") (pintype "bidirectional"))
      (node (ref "CHIP_4") (pin "P3") (pinfunction "LAT_P3") (pintype "bidirectional"))
      (node (ref "CHIP_5") (pin "P3") (pinfunction "LAT_P3") (pintype "bidirectional"))
      (node (ref "CHIP_6") (pin "P3") (pinfunction "LAT_P3") (pintype "bidirectional"))
      (node (ref "INPUT") (pin "4") (pinfunction "4_4") (pintype "passive"))
      (node (ref "OUTPUT") (pin "4") (pinfunction "4_4") (pintype "passive"))
    )
    (net (code "5") (name "/SCLK") (class "Default")
      (node (ref "CHIP_1") (pin "P2") (pinfunction "SCLK_P2") (pintype "bidirectional"))
      (node (ref "CHIP_2") (pin "P2") (pinfunction "SCLK_P2") (pintype "bidirectional"))
      (node (ref "CHIP_3") (pin "P2") (pinfunction "SCLK_P2") (pintype "bidirectional"))
      (node (ref "CHIP_4") (pin "P2") (pinfunction "SCLK_P2") (pintype "bidirectional"))
      (node (ref "CHIP_5") (pin "P2") (pinfunction "SCLK_P2") (pintype "bidirectional"))
      (node (ref "CHIP_6") (pin "P2") (pinfunction "SCLK_P2") (pintype "bidirectional"))
      (node (ref "INPUT") (pin "3") (pinfunction "3_3") (pintype "passive"))
      (node (ref "OUTPUT") (pin "3") (pinfunction "3_3") (pintype "passive"))
    )
    (net (code "6") (name "GND") (class "Default")
      (node (ref "C1") (pin "1") (pinfunction "1_1") (pintype "passive"))
      (node (ref "C2") (pin "1") (pinfunction "1_1") (pintype "passive"))
      (node (ref "C3") (pin "1") (pinfunction "1_1") (pintype "passive"))
      (node (ref "C4") (pin "1") (pinfunction "1_1") (pintype "passive"))
      (node (ref "C5") (pin "1") (pinfunction "1_1") (pintype "passive"))
      (node (ref "C6") (pin "1") (pinfunction "1_1") (pintype "passive"))
      (node (ref "CHIP_1") (pin "P29") (pinfunction "GND2_P29") (pintype "bidirectional"))
      (node (ref "CHIP_1") (pin "P56") (pinfunction "GND_P56") (pintype "bidirectional"))
      (node (ref "CHIP_2") (pin "P29") (pinfunction "GND2_P29") (pintype "bidirectional"))
      (node (ref "CHIP_2") (pin "P56") (pinfunction "GND_P56") (pintype "bidirectional"))
      (node (ref "CHIP_3") (pin "P29") (pinfunction "GND2_P29") (pintype "bidirectional"))
      (node (ref "CHIP_3") (pin "P56") (pinfunction "GND_P56") (pintype "bidirectional"))
      (node (ref "CHIP_4") (pin "P29") (pinfunction "GND2_P29") (pintype "bidirectional"))
      (node (ref "CHIP_4") (pin "P56") (pinfunction "GND_P56") (pintype "bidirectional"))
      (node (ref "CHIP_5") (pin "P29") (pinfunction "GND2_P29") (pintype "bidirectional"))
      (node (ref "CHIP_5") (pin "P56") (pinfunction "GND_P56") (pintype "bidirectional"))
      (node (ref "CHIP_6") (pin "P29") (pinfunction "GND2_P29") (pintype "bidirectional"))
      (node (ref "CHIP_6") (pin "P56") (pinfunction "GND_P56") (pintype "bidirectional"))
      (node (ref "INPUT") (pin "1") (pinfunction "1_1") (pintype "passive"))
      (node (ref "OUTPUT") (pin "1") (pinfunction "1_1") (pintype "passive"))
      (node (ref "SOUT1") (pin "2") (pinfunction "2_2") (pintype "passive"))
      (node (ref "SOUT2") (pin "2") (pinfunction "2_2") (pintype "passive"))
      (node (ref "SOUT3") (pin "2") (pinfunction "2_2") (pintype "passive"))
      (node (ref "SOUT4") (pin "2") (pinfunction "2_2") (pintype "passive"))
      (node (ref "SOUT5") (pin "2") (pinfunction "2_2") (pintype "passive"))
      (node (ref "SOUT6") (pin "2") (pinfunction "2_2") (pintype "passive"))
      (node (ref "U$1") (pin "P$1") (pinfunction "GND_P$1") (pintype "bidirectional"))
    )
    (net (code "7") (name "Net-(CHIP_1-B0)") (class "Default")
      (node (ref "CHIP_1") (pin "P7") (pinfunction "B0_P7") (pintype "bidirectional"))
      (node (ref "D58") (pin "4") (pinfunction "BLUE_CATHODE_4") (pintype "bidirectional"))
    )
    (net (code "8") (name "Net-(CHIP_1-B1)") (class "Default")
      (node (ref "CHIP_1") (pin "P13") (pinfunction "B1_P13") (pintype "bidirectional"))
      (node (ref "D59") (pin "4") (pinfunction "BLUE_CATHODE_4") (pintype "bidirectional"))
    )
    (net (code "9") (name "Net-(CHIP_1-B2)") (class "Default")
      (node (ref "CHIP_1") (pin "P16") (pinfunction "B2_P16") (pintype "bidirectional"))
      (node (ref "D55") (pin "4") (pinfunction "BLUE_CATHODE_4") (pintype "bidirectional"))
    )
    (net (code "10") (name "Net-(CHIP_1-B3)") (class "Default")
      (node (ref "CHIP_1") (pin "P22") (pinfunction "B3_P22") (pintype "bidirectional"))
      (node (ref "D63") (pin "4") (pinfunction "BLUE_CATHODE_4") (pintype "bidirectional"))
    )
    (net (code "11") (name "Net-(CHIP_1-B4)") (class "Default")
      (node (ref "CHIP_1") (pin "P4") (pinfunction "B4_P4") (pintype "bidirectional"))
      (node (ref "D64") (pin "4") (pinfunction "BLUE_CATHODE_4") (pintype "bidirectional"))
    )
    (net (code "12") (name "Net-(CHIP_1-B5)") (class "Default")
      (node (ref "CHIP_1") (pin "P10") (pinfunction "B5_P10") (pintype "bidirectional"))
      (node (ref "D56") (pin "4") (pinfunction "BLUE_CATHODE_4") (pintype "bidirectional"))
    )
    (net (code "13") (name "Net-(CHIP_1-B6)") (class "Default")
      (node (ref "CHIP_1") (pin "P19") (pinfunction "B6_P19") (pintype "bidirectional"))
      (node (ref "D51") (pin "4") (pinfunction "BLUE_CATHODE_4") (pintype "bidirectional"))
    )
    (net (code "14") (name "Net-(CHIP_1-B7)") (class "Default")
      (node (ref "CHIP_1") (pin "P25") (pinfunction "B7_P25") (pintype "bidirectional"))
      (node (ref "D60") (pin "4") (pinfunction "BLUE_CATHODE_4") (pintype "bidirectional"))
    )
    (net (code "15") (name "Net-(CHIP_1-B8)") (class "Default")
      (node (ref "CHIP_1") (pin "P53") (pinfunction "B8_P53") (pintype "bidirectional"))
      (node (ref "D53") (pin "4") (pinfunction "BLUE_CATHODE_4") (pintype "bidirectional"))
    )
    (net (code "16") (name "Net-(CHIP_1-B9)") (class "Default")
      (node (ref "CHIP_1") (pin "P47") (pinfunction "B9_P47") (pintype "bidirectional"))
      (node (ref "D54") (pin "4") (pinfunction "BLUE_CATHODE_4") (pintype "bidirectional"))
    )
    (net (code "17") (name "Net-(CHIP_1-B10)") (class "Default")
      (node (ref "CHIP_1") (pin "P38") (pinfunction "B10_P38") (pintype "bidirectional"))
      (node (ref "D50") (pin "4") (pinfunction "BLUE_CATHODE_4") (pintype "bidirectional"))
    )
    (net (code "18") (name "Net-(CHIP_1-B11)") (class "Default")
      (node (ref "CHIP_1") (pin "P32") (pinfunction "B11_P32") (pintype "bidirectional"))
      (node (ref "D52") (pin "4") (pinfunction "BLUE_CATHODE_4") (pintype "bidirectional"))
    )
    (net (code "19") (name "Net-(CHIP_1-B12)") (class "Default")
      (node (ref "CHIP_1") (pin "P50") (pinfunction "B12_P50") (pintype "bidirectional"))
      (node (ref "D62") (pin "4") (pinfunction "BLUE_CATHODE_4") (pintype "bidirectional"))
    )
    (net (code "20") (name "Net-(CHIP_1-B13)") (class "Default")
      (node (ref "CHIP_1") (pin "P44") (pinfunction "B13_P44") (pintype "bidirectional"))
      (node (ref "D61") (pin "4") (pinfunction "BLUE_CATHODE_4") (pintype "bidirectional"))
    )
    (net (code "21") (name "Net-(CHIP_1-B14)") (class "Default")
      (node (ref "CHIP_1") (pin "P41") (pinfunction "B14_P41") (pintype "bidirectional"))
      (node (ref "D49") (pin "4") (pinfunction "BLUE_CATHODE_4") (pintype "bidirectional"))
    )
    (net (code "22") (name "Net-(CHIP_1-B15)") (class "Default")
      (node (ref "CHIP_1") (pin "P35") (pinfunction "B15_P35") (pintype "bidirectional"))
      (node (ref "D57") (pin "4") (pinfunction "BLUE_CATHODE_4") (pintype "bidirectional"))
    )
    (net (code "23") (name "Net-(CHIP_1-G0)") (class "Default")
      (node (ref "CHIP_1") (pin "P9") (pinfunction "G0_P9") (pintype "bidirectional"))
      (node (ref "D58") (pin "1") (pinfunction "GREEN_CATHODE_1") (pintype "bidirectional"))
    )
    (net (code "24") (name "Net-(CHIP_1-G1)") (class "Default")
      (node (ref "CHIP_1") (pin "P15") (pinfunction "G1_P15") (pintype "bidirectional"))
      (node (ref "D59") (pin "1") (pinfunction "GREEN_CATHODE_1") (pintype "bidirectional"))
    )
    (net (code "25") (name "Net-(CHIP_1-G2)") (class "Default")
      (node (ref "CHIP_1") (pin "P18") (pinfunction "G2_P18") (pintype "bidirectional"))
      (node (ref "D55") (pin "1") (pinfunction "GREEN_CATHODE_1") (pintype "bidirectional"))
    )
    (net (code "26") (name "Net-(CHIP_1-G3)") (class "Default")
      (node (ref "CHIP_1") (pin "P24") (pinfunction "G3_P24") (pintype "bidirectional"))
      (node (ref "D63") (pin "1") (pinfunction "GREEN_CATHODE_1") (pintype "bidirectional"))
    )
    (net (code "27") (name "Net-(CHIP_1-G4)") (class "Default")
      (node (ref "CHIP_1") (pin "P6") (pinfunction "G4_P6") (pintype "bidirectional"))
      (node (ref "D64") (pin "1") (pinfunction "GREEN_CATHODE_1") (pintype "bidirectional"))
    )
    (net (code "28") (name "Net-(CHIP_1-G5)") (class "Default")
      (node (ref "CHIP_1") (pin "P12") (pinfunction "G5_P12") (pintype "bidirectional"))
      (node (ref "D56") (pin "1") (pinfunction "GREEN_CATHODE_1") (pintype "bidirectional"))
    )
    (net (code "29") (name "Net-(CHIP_1-G6)") (class "Default")
      (node (ref "CHIP_1") (pin "P21") (pinfunction "G6_P21") (pintype "bidirectional"))
      (node (ref "D51") (pin "1") (pinfunction "GREEN_CATHODE_1") (pintype "bidirectional"))
    )
    (net (code "30") (name "Net-(CHIP_1-G7)") (class "Default")
      (node (ref "CHIP_1") (pin "P27") (pinfunction "G7_P27") (pintype "bidirectional"))
      (node (ref "D60") (pin "1") (pinfunction "GREEN_CATHODE_1") (pintype "bidirectional"))
    )
    (net (code "31") (name "Net-(CHIP_1-G8)") (class "Default")
      (node (ref "CHIP_1") (pin "P51") (pinfunction "G8_P51") (pintype "bidirectional"))
      (node (ref "D53") (pin "1") (pinfunction "GREEN_CATHODE_1") (pintype "bidirectional"))
    )
    (net (code "32") (name "Net-(CHIP_1-G9)") (class "Default")
      (node (ref "CHIP_1") (pin "P45") (pinfunction "G9_P45") (pintype "bidirectional"))
      (node (ref "D54") (pin "1") (pinfunction "GREEN_CATHODE_1") (pintype "bidirectional"))
    )
    (net (code "33") (name "Net-(CHIP_1-G10)") (class "Default")
      (node (ref "CHIP_1") (pin "P36") (pinfunction "G10_P36") (pintype "bidirectional"))
      (node (ref "D50") (pin "1") (pinfunction "GREEN_CATHODE_1") (pintype "bidirectional"))
    )
    (net (code "34") (name "Net-(CHIP_1-G11)") (class "Default")
      (node (ref "CHIP_1") (pin "P30") (pinfunction "G11_P30") (pintype "bidirectional"))
      (node (ref "D52") (pin "1") (pinfunction "GREEN_CATHODE_1") (pintype "bidirectional"))
    )
    (net (code "35") (name "Net-(CHIP_1-G12)") (class "Default")
      (node (ref "CHIP_1") (pin "P48") (pinfunction "G12_P48") (pintype "bidirectional"))
      (node (ref "D62") (pin "1") (pinfunction "GREEN_CATHODE_1") (pintype "bidirectional"))
    )
    (net (code "36") (name "Net-(CHIP_1-G13)") (class "Default")
      (node (ref "CHIP_1") (pin "P42") (pinfunction "G13_P42") (pintype "bidirectional"))
      (node (ref "D61") (pin "1") (pinfunction "GREEN_CATHODE_1") (pintype "bidirectional"))
    )
    (net (code "37") (name "Net-(CHIP_1-G14)") (class "Default")
      (node (ref "CHIP_1") (pin "P39") (pinfunction "G14_P39") (pintype "bidirectional"))
      (node (ref "D49") (pin "1") (pinfunction "GREEN_CATHODE_1") (pintype "bidirectional"))
    )
    (net (code "38") (name "Net-(CHIP_1-G15)") (class "Default")
      (node (ref "CHIP_1") (pin "P33") (pinfunction "G15_P33") (pintype "bidirectional"))
      (node (ref "D57") (pin "1") (pinfunction "GREEN_CATHODE_1") (pintype "bidirectional"))
    )
    (net (code "39") (name "Net-(CHIP_1-R0)") (class "Default")
      (node (ref "CHIP_1") (pin "P8") (pinfunction "R0_P8") (pintype "bidirectional"))
      (node (ref "D58") (pin "3") (pinfunction "RED_CATHODE_3") (pintype "bidirectional"))
    )
    (net (code "40") (name "Net-(CHIP_1-R1)") (class "Default")
      (node (ref "CHIP_1") (pin "P14") (pinfunction "R1_P14") (pintype "bidirectional"))
      (node (ref "D59") (pin "3") (pinfunction "RED_CATHODE_3") (pintype "bidirectional"))
    )
    (net (code "41") (name "Net-(CHIP_1-R2)") (class "Default")
      (node (ref "CHIP_1") (pin "P17") (pinfunction "R2_P17") (pintype "bidirectional"))
      (node (ref "D55") (pin "3") (pinfunction "RED_CATHODE_3") (pintype "bidirectional"))
    )
    (net (code "42") (name "Net-(CHIP_1-R3)") (class "Default")
      (node (ref "CHIP_1") (pin "P23") (pinfunction "R3_P23") (pintype "bidirectional"))
      (node (ref "D63") (pin "3") (pinfunction "RED_CATHODE_3") (pintype "bidirectional"))
    )
    (net (code "43") (name "Net-(CHIP_1-R4)") (class "Default")
      (node (ref "CHIP_1") (pin "P5") (pinfunction "R4_P5") (pintype "bidirectional"))
      (node (ref "D64") (pin "3") (pinfunction "RED_CATHODE_3") (pintype "bidirectional"))
    )
    (net (code "44") (name "Net-(CHIP_1-R5)") (class "Default")
      (node (ref "CHIP_1") (pin "P11") (pinfunction "R5_P11") (pintype "bidirectional"))
      (node (ref "D56") (pin "3") (pinfunction "RED_CATHODE_3") (pintype "bidirectional"))
    )
    (net (code "45") (name "Net-(CHIP_1-R6)") (class "Default")
      (node (ref "CHIP_1") (pin "P20") (pinfunction "R6_P20") (pintype "bidirectional"))
      (node (ref "D51") (pin "3") (pinfunction "RED_CATHODE_3") (pintype "bidirectional"))
    )
    (net (code "46") (name "Net-(CHIP_1-R7)") (class "Default")
      (node (ref "CHIP_1") (pin "P26") (pinfunction "R7_P26") (pintype "bidirectional"))
      (node (ref "D60") (pin "3") (pinfunction "RED_CATHODE_3") (pintype "bidirectional"))
    )
    (net (code "47") (name "Net-(CHIP_1-R8)") (class "Default")
      (node (ref "CHIP_1") (pin "P52") (pinfunction "R8_P52") (pintype "bidirectional"))
      (node (ref "D53") (pin "3") (pinfunction "RED_CATHODE_3") (pintype "bidirectional"))
    )
    (net (code "48") (name "Net-(CHIP_1-R9)") (class "Default")
      (node (ref "CHIP_1") (pin "P46") (pinfunction "R9_P46") (pintype "bidirectional"))
      (node (ref "D54") (pin "3") (pinfunction "RED_CATHODE_3") (pintype "bidirectional"))
    )
    (net (code "49") (name "Net-(CHIP_1-R10)") (class "Default")
      (node (ref "CHIP_1") (pin "P37") (pinfunction "R10_P37") (pintype "bidirectional"))
      (node (ref "D50") (pin "3") (pinfunction "RED_CATHODE_3") (pintype "bidirectional"))
    )
    (net (code "50") (name "Net-(CHIP_1-R11)") (class "Default")
      (node (ref "CHIP_1") (pin "P31") (pinfunction "R11_P31") (pintype "bidirectional"))
      (node (ref "D52") (pin "3") (pinfunction "RED_CATHODE_3") (pintype "bidirectional"))
    )
    (net (code "51") (name "Net-(CHIP_1-R12)") (class "Default")
      (node (ref "CHIP_1") (pin "P49") (pinfunction "R12_P49") (pintype "bidirectional"))
      (node (ref "D62") (pin "3") (pinfunction "RED_CATHODE_3") (pintype "bidirectional"))
    )
    (net (code "52") (name "Net-(CHIP_1-R13)") (class "Default")
      (node (ref "CHIP_1") (pin "P43") (pinfunction "R13_P43") (pintype "bidirectional"))
      (node (ref "D61") (pin "3") (pinfunction "RED_CATHODE_3") (pintype "bidirectional"))
    )
    (net (code "53") (name "Net-(CHIP_1-R14)") (class "Default")
      (node (ref "CHIP_1") (pin "P40") (pinfunction "R14_P40") (pintype "bidirectional"))
      (node (ref "D49") (pin "3") (pinfunction "RED_CATHODE_3") (pintype "bidirectional"))
    )
    (net (code "54") (name "Net-(CHIP_1-R15)") (class "Default")
      (node (ref "CHIP_1") (pin "P34") (pinfunction "R15_P34") (pintype "bidirectional"))
      (node (ref "D57") (pin "3") (pinfunction "RED_CATHODE_3") (pintype "bidirectional"))
    )
    (net (code "55") (name "Net-(CHIP_1-SOUT)") (class "Default")
      (node (ref "CHIP_1") (pin "P28") (pinfunction "SOUT_P28") (pintype "bidirectional"))
      (node (ref "CHIP_2") (pin "P1") (pinfunction "SIN_P1") (pintype "bidirectional"))
      (node (ref "SOUT1") (pin "1") (pinfunction "1_1") (pintype "passive"))
    )
    (net (code "56") (name "Net-(CHIP_2-B0)") (class "Default")
      (node (ref "CHIP_2") (pin "P7") (pinfunction "B0_P7") (pintype "bidirectional"))
      (node (ref "D74") (pin "4") (pinfunction "BLUE_CATHODE_4") (pintype "bidirectional"))
    )
    (net (code "57") (name "Net-(CHIP_2-B1)") (class "Default")
      (node (ref "CHIP_2") (pin "P13") (pinfunction "B1_P13") (pintype "bidirectional"))
      (node (ref "D75") (pin "4") (pinfunction "BLUE_CATHODE_4") (pintype "bidirectional"))
    )
    (net (code "58") (name "Net-(CHIP_2-B2)") (class "Default")
      (node (ref "CHIP_2") (pin "P16") (pinfunction "B2_P16") (pintype "bidirectional"))
      (node (ref "D71") (pin "4") (pinfunction "BLUE_CATHODE_4") (pintype "bidirectional"))
    )
    (net (code "59") (name "Net-(CHIP_2-B3)") (class "Default")
      (node (ref "CHIP_2") (pin "P22") (pinfunction "B3_P22") (pintype "bidirectional"))
      (node (ref "D79") (pin "4") (pinfunction "BLUE_CATHODE_4") (pintype "bidirectional"))
    )
    (net (code "60") (name "Net-(CHIP_2-B4)") (class "Default")
      (node (ref "CHIP_2") (pin "P4") (pinfunction "B4_P4") (pintype "bidirectional"))
      (node (ref "D80") (pin "4") (pinfunction "BLUE_CATHODE_4") (pintype "bidirectional"))
    )
    (net (code "61") (name "Net-(CHIP_2-B5)") (class "Default")
      (node (ref "CHIP_2") (pin "P10") (pinfunction "B5_P10") (pintype "bidirectional"))
      (node (ref "D72") (pin "4") (pinfunction "BLUE_CATHODE_4") (pintype "bidirectional"))
    )
    (net (code "62") (name "Net-(CHIP_2-B6)") (class "Default")
      (node (ref "CHIP_2") (pin "P19") (pinfunction "B6_P19") (pintype "bidirectional"))
      (node (ref "D67") (pin "4") (pinfunction "BLUE_CATHODE_4") (pintype "bidirectional"))
    )
    (net (code "63") (name "Net-(CHIP_2-B7)") (class "Default")
      (node (ref "CHIP_2") (pin "P25") (pinfunction "B7_P25") (pintype "bidirectional"))
      (node (ref "D76") (pin "4") (pinfunction "BLUE_CATHODE_4") (pintype "bidirectional"))
    )
    (net (code "64") (name "Net-(CHIP_2-B8)") (class "Default")
      (node (ref "CHIP_2") (pin "P53") (pinfunction "B8_P53") (pintype "bidirectional"))
      (node (ref "D69") (pin "4") (pinfunction "BLUE_CATHODE_4") (pintype "bidirectional"))
    )
    (net (code "65") (name "Net-(CHIP_2-B9)") (class "Default")
      (node (ref "CHIP_2") (pin "P47") (pinfunction "B9_P47") (pintype "bidirectional"))
      (node (ref "D70") (pin "4") (pinfunction "BLUE_CATHODE_4") (pintype "bidirectional"))
    )
    (net (code "66") (name "Net-(CHIP_2-B10)") (class "Default")
      (node (ref "CHIP_2") (pin "P38") (pinfunction "B10_P38") (pintype "bidirectional"))
      (node (ref "D66") (pin "4") (pinfunction "BLUE_CATHODE_4") (pintype "bidirectional"))
    )
    (net (code "67") (name "Net-(CHIP_2-B11)") (class "Default")
      (node (ref "CHIP_2") (pin "P32") (pinfunction "B11_P32") (pintype "bidirectional"))
      (node (ref "D68") (pin "4") (pinfunction "BLUE_CATHODE_4") (pintype "bidirectional"))
    )
    (net (code "68") (name "Net-(CHIP_2-B12)") (class "Default")
      (node (ref "CHIP_2") (pin "P50") (pinfunction "B12_P50") (pintype "bidirectional"))
      (node (ref "D78") (pin "4") (pinfunction "BLUE_CATHODE_4") (pintype "bidirectional"))
    )
    (net (code "69") (name "Net-(CHIP_2-B13)") (class "Default")
      (node (ref "CHIP_2") (pin "P44") (pinfunction "B13_P44") (pintype "bidirectional"))
      (node (ref "D77") (pin "4") (pinfunction "BLUE_CATHODE_4") (pintype "bidirectional"))
    )
    (net (code "70") (name "Net-(CHIP_2-B14)") (class "Default")
      (node (ref "CHIP_2") (pin "P41") (pinfunction "B14_P41") (pintype "bidirectional"))
      (node (ref "D65") (pin "4") (pinfunction "BLUE_CATHODE_4") (pintype "bidirectional"))
    )
    (net (code "71") (name "Net-(CHIP_2-B15)") (class "Default")
      (node (ref "CHIP_2") (pin "P35") (pinfunction "B15_P35") (pintype "bidirectional"))
      (node (ref "D73") (pin "4") (pinfunction "BLUE_CATHODE_4") (pintype "bidirectional"))
    )
    (net (code "72") (name "Net-(CHIP_2-G0)") (class "Default")
      (node (ref "CHIP_2") (pin "P9") (pinfunction "G0_P9") (pintype "bidirectional"))
      (node (ref "D74") (pin "1") (pinfunction "GREEN_CATHODE_1") (pintype "bidirectional"))
    )
    (net (code "73") (name "Net-(CHIP_2-G1)") (class "Default")
      (node (ref "CHIP_2") (pin "P15") (pinfunction "G1_P15") (pintype "bidirectional"))
      (node (ref "D75") (pin "1") (pinfunction "GREEN_CATHODE_1") (pintype "bidirectional"))
    )
    (net (code "74") (name "Net-(CHIP_2-G2)") (class "Default")
      (node (ref "CHIP_2") (pin "P18") (pinfunction "G2_P18") (pintype "bidirectional"))
      (node (ref "D71") (pin "1") (pinfunction "GREEN_CATHODE_1") (pintype "bidirectional"))
    )
    (net (code "75") (name "Net-(CHIP_2-G3)") (class "Default")
      (node (ref "CHIP_2") (pin "P24") (pinfunction "G3_P24") (pintype "bidirectional"))
      (node (ref "D79") (pin "1") (pinfunction "GREEN_CATHODE_1") (pintype "bidirectional"))
    )
    (net (code "76") (name "Net-(CHIP_2-G4)") (class "Default")
      (node (ref "CHIP_2") (pin "P6") (pinfunction "G4_P6") (pintype "bidirectional"))
      (node (ref "D80") (pin "1") (pinfunction "GREEN_CATHODE_1") (pintype "bidirectional"))
    )
    (net (code "77") (name "Net-(CHIP_2-G5)") (class "Default")
      (node (ref "CHIP_2") (pin "P12") (pinfunction "G5_P12") (pintype "bidirectional"))
      (node (ref "D72") (pin "1") (pinfunction "GREEN_CATHODE_1") (pintype "bidirectional"))
    )
    (net (code "78") (name "Net-(CHIP_2-G6)") (class "Default")
      (node (ref "CHIP_2") (pin "P21") (pinfunction "G6_P21") (pintype "bidirectional"))
      (node (ref "D67") (pin "1") (pinfunction "GREEN_CATHODE_1") (pintype "bidirectional"))
    )
    (net (code "79") (name "Net-(CHIP_2-G7)") (class "Default")
      (node (ref "CHIP_2") (pin "P27") (pinfunction "G7_P27") (pintype "bidirectional"))
      (node (ref "D76") (pin "1") (pinfunction "GREEN_CATHODE_1") (pintype "bidirectional"))
    )
    (net (code "80") (name "Net-(CHIP_2-G8)") (class "Default")
      (node (ref "CHIP_2") (pin "P51") (pinfunction "G8_P51") (pintype "bidirectional"))
      (node (ref "D69") (pin "1") (pinfunction "GREEN_CATHODE_1") (pintype "bidirectional"))
    )
    (net (code "81") (name "Net-(CHIP_2-G9)") (class "Default")
      (node (ref "CHIP_2") (pin "P45") (pinfunction "G9_P45") (pintype "bidirectional"))
      (node (ref "D70") (pin "1") (pinfunction "GREEN_CATHODE_1") (pintype "bidirectional"))
    )
    (net (code "82") (name "Net-(CHIP_2-G10)") (class "Default")
      (node (ref "CHIP_2") (pin "P36") (pinfunction "G10_P36") (pintype "bidirectional"))
      (node (ref "D66") (pin "1") (pinfunction "GREEN_CATHODE_1") (pintype "bidirectional"))
    )
    (net (code "83") (name "Net-(CHIP_2-G11)") (class "Default")
      (node (ref "CHIP_2") (pin "P30") (pinfunction "G11_P30") (pintype "bidirectional"))
      (node (ref "D68") (pin "1") (pinfunction "GREEN_CATHODE_1") (pintype "bidirectional"))
    )
    (net (code "84") (name "Net-(CHIP_2-G12)") (class "Default")
      (node (ref "CHIP_2") (pin "P48") (pinfunction "G12_P48") (pintype "bidirectional"))
      (node (ref "D78") (pin "1") (pinfunction "GREEN_CATHODE_1") (pintype "bidirectional"))
    )
    (net (code "85") (name "Net-(CHIP_2-G13)") (class "Default")
      (node (ref "CHIP_2") (pin "P42") (pinfunction "G13_P42") (pintype "bidirectional"))
      (node (ref "D77") (pin "1") (pinfunction "GREEN_CATHODE_1") (pintype "bidirectional"))
    )
    (net (code "86") (name "Net-(CHIP_2-G14)") (class "Default")
      (node (ref "CHIP_2") (pin "P39") (pinfunction "G14_P39") (pintype "bidirectional"))
      (node (ref "D65") (pin "1") (pinfunction "GREEN_CATHODE_1") (pintype "bidirectional"))
    )
    (net (code "87") (name "Net-(CHIP_2-G15)") (class "Default")
      (node (ref "CHIP_2") (pin "P33") (pinfunction "G15_P33") (pintype "bidirectional"))
      (node (ref "D73") (pin "1") (pinfunction "GREEN_CATHODE_1") (pintype "bidirectional"))
    )
    (net (code "88") (name "Net-(CHIP_2-R0)") (class "Default")
      (node (ref "CHIP_2") (pin "P8") (pinfunction "R0_P8") (pintype "bidirectional"))
      (node (ref "D74") (pin "3") (pinfunction "RED_CATHODE_3") (pintype "bidirectional"))
    )
    (net (code "89") (name "Net-(CHIP_2-R1)") (class "Default")
      (node (ref "CHIP_2") (pin "P14") (pinfunction "R1_P14") (pintype "bidirectional"))
      (node (ref "D75") (pin "3") (pinfunction "RED_CATHODE_3") (pintype "bidirectional"))
    )
    (net (code "90") (name "Net-(CHIP_2-R2)") (class "Default")
      (node (ref "CHIP_2") (pin "P17") (pinfunction "R2_P17") (pintype "bidirectional"))
      (node (ref "D71") (pin "3") (pinfunction "RED_CATHODE_3") (pintype "bidirectional"))
    )
    (net (code "91") (name "Net-(CHIP_2-R3)") (class "Default")
      (node (ref "CHIP_2") (pin "P23") (pinfunction "R3_P23") (pintype "bidirectional"))
      (node (ref "D79") (pin "3") (pinfunction "RED_CATHODE_3") (pintype "bidirectional"))
    )
    (net (code "92") (name "Net-(CHIP_2-R4)") (class "Default")
      (node (ref "CHIP_2") (pin "P5") (pinfunction "R4_P5") (pintype "bidirectional"))
      (node (ref "D80") (pin "3") (pinfunction "RED_CATHODE_3") (pintype "bidirectional"))
    )
    (net (code "93") (name "Net-(CHIP_2-R5)") (class "Default")
      (node (ref "CHIP_2") (pin "P11") (pinfunction "R5_P11") (pintype "bidirectional"))
      (node (ref "D72") (pin "3") (pinfunction "RED_CATHODE_3") (pintype "bidirectional"))
    )
    (net (code "94") (name "Net-(CHIP_2-R6)") (class "Default")
      (node (ref "CHIP_2") (pin "P20") (pinfunction "R6_P20") (pintype "bidirectional"))
      (node (ref "D67") (pin "3") (pinfunction "RED_CATHODE_3") (pintype "bidirectional"))
    )
    (net (code "95") (name "Net-(CHIP_2-R7)") (class "Default")
      (node (ref "CHIP_2") (pin "P26") (pinfunction "R7_P26") (pintype "bidirectional"))
      (node (ref "D76") (pin "3") (pinfunction "RED_CATHODE_3") (pintype "bidirectional"))
    )
    (net (code "96") (name "Net-(CHIP_2-R8)") (class "Default")
      (node (ref "CHIP_2") (pin "P52") (pinfunction "R8_P52") (pintype "bidirectional"))
      (node (ref "D69") (pin "3") (pinfunction "RED_CATHODE_3") (pintype "bidirectional"))
    )
    (net (code "97") (name "Net-(CHIP_2-R9)") (class "Default")
      (node (ref "CHIP_2") (pin "P46") (pinfunction "R9_P46") (pintype "bidirectional"))
      (node (ref "D70") (pin "3") (pinfunction "RED_CATHODE_3") (pintype "bidirectional"))
    )
    (net (code "98") (name "Net-(CHIP_2-R10)") (class "Default")
      (node (ref "CHIP_2") (pin "P37") (pinfunction "R10_P37") (pintype "bidirectional"))
      (node (ref "D66") (pin "3") (pinfunction "RED_CATHODE_3") (pintype "bidirectional"))
    )
    (net (code "99") (name "Net-(CHIP_2-R11)") (class "Default")
      (node (ref "CHIP_2") (pin "P31") (pinfunction "R11_P31") (pintype "bidirectional"))
      (node (ref "D68") (pin "3") (pinfunction "RED_CATHODE_3") (pintype "bidirectional"))
    )
    (net (code "100") (name "Net-(CHIP_2-R12)") (class "Default")
      (node (ref "CHIP_2") (pin "P49") (pinfunction "R12_P49") (pintype "bidirectional"))
      (node (ref "D78") (pin "3") (pinfunction "RED_CATHODE_3") (pintype "bidirectional"))
    )
    (net (code "101") (name "Net-(CHIP_2-R13)") (class "Default")
      (node (ref "CHIP_2") (pin "P43") (pinfunction "R13_P43") (pintype "bidirectional"))
      (node (ref "D77") (pin "3") (pinfunction "RED_CATHODE_3") (pintype "bidirectional"))
    )
    (net (code "102") (name "Net-(CHIP_2-R14)") (class "Default")
      (node (ref "CHIP_2") (pin "P40") (pinfunction "R14_P40") (pintype "bidirectional"))
      (node (ref "D65") (pin "3") (pinfunction "RED_CATHODE_3") (pintype "bidirectional"))
    )
    (net (code "103") (name "Net-(CHIP_2-R15)") (class "Default")
      (node (ref "CHIP_2") (pin "P34") (pinfunction "R15_P34") (pintype "bidirectional"))
      (node (ref "D73") (pin "3") (pinfunction "RED_CATHODE_3") (pintype "bidirectional"))
    )
    (net (code "104") (name "Net-(CHIP_2-SOUT)") (class "Default")
      (node (ref "CHIP_2") (pin "P28") (pinfunction "SOUT_P28") (pintype "bidirectional"))
      (node (ref "CHIP_3") (pin "P1") (pinfunction "SIN_P1") (pintype "bidirectional"))
      (node (ref "SOUT2") (pin "1") (pinfunction "1_1") (pintype "passive"))
    )
    (net (code "105") (name "Net-(CHIP_3-B0)") (class "Default")
      (node (ref "CHIP_3") (pin "P7") (pinfunction "B0_P7") (pintype "bidirectional"))
      (node (ref "D90") (pin "4") (pinfunction "BLUE_CATHODE_4") (pintype "bidirectional"))
    )
    (net (code "106") (name "Net-(CHIP_3-B1)") (class "Default")
      (node (ref "CHIP_3") (pin "P13") (pinfunction "B1_P13") (pintype "bidirectional"))
      (node (ref "D91") (pin "4") (pinfunction "BLUE_CATHODE_4") (pintype "bidirectional"))
    )
    (net (code "107") (name "Net-(CHIP_3-B2)") (class "Default")
      (node (ref "CHIP_3") (pin "P16") (pinfunction "B2_P16") (pintype "bidirectional"))
      (node (ref "D87") (pin "4") (pinfunction "BLUE_CATHODE_4") (pintype "bidirectional"))
    )
    (net (code "108") (name "Net-(CHIP_3-B3)") (class "Default")
      (node (ref "CHIP_3") (pin "P22") (pinfunction "B3_P22") (pintype "bidirectional"))
      (node (ref "D95") (pin "4") (pinfunction "BLUE_CATHODE_4") (pintype "bidirectional"))
    )
    (net (code "109") (name "Net-(CHIP_3-B4)") (class "Default")
      (node (ref "CHIP_3") (pin "P4") (pinfunction "B4_P4") (pintype "bidirectional"))
      (node (ref "D96") (pin "4") (pinfunction "BLUE_CATHODE_4") (pintype "bidirectional"))
    )
    (net (code "110") (name "Net-(CHIP_3-B5)") (class "Default")
      (node (ref "CHIP_3") (pin "P10") (pinfunction "B5_P10") (pintype "bidirectional"))
      (node (ref "D88") (pin "4") (pinfunction "BLUE_CATHODE_4") (pintype "bidirectional"))
    )
    (net (code "111") (name "Net-(CHIP_3-B6)") (class "Default")
      (node (ref "CHIP_3") (pin "P19") (pinfunction "B6_P19") (pintype "bidirectional"))
      (node (ref "D83") (pin "4") (pinfunction "BLUE_CATHODE_4") (pintype "bidirectional"))
    )
    (net (code "112") (name "Net-(CHIP_3-B7)") (class "Default")
      (node (ref "CHIP_3") (pin "P25") (pinfunction "B7_P25") (pintype "bidirectional"))
      (node (ref "D92") (pin "4") (pinfunction "BLUE_CATHODE_4") (pintype "bidirectional"))
    )
    (net (code "113") (name "Net-(CHIP_3-B8)") (class "Default")
      (node (ref "CHIP_3") (pin "P53") (pinfunction "B8_P53") (pintype "bidirectional"))
      (node (ref "D85") (pin "4") (pinfunction "BLUE_CATHODE_4") (pintype "bidirectional"))
    )
    (net (code "114") (name "Net-(CHIP_3-B9)") (class "Default")
      (node (ref "CHIP_3") (pin "P47") (pinfunction "B9_P47") (pintype "bidirectional"))
      (node (ref "D86") (pin "4") (pinfunction "BLUE_CATHODE_4") (pintype "bidirectional"))
    )
    (net (code "115") (name "Net-(CHIP_3-B10)") (class "Default")
      (node (ref "CHIP_3") (pin "P38") (pinfunction "B10_P38") (pintype "bidirectional"))
      (node (ref "D82") (pin "4") (pinfunction "BLUE_CATHODE_4") (pintype "bidirectional"))
    )
    (net (code "116") (name "Net-(CHIP_3-B11)") (class "Default")
      (node (ref "CHIP_3") (pin "P32") (pinfunction "B11_P32") (pintype "bidirectional"))
      (node (ref "D84") (pin "4") (pinfunction "BLUE_CATHODE_4") (pintype "bidirectional"))
    )
    (net (code "117") (name "Net-(CHIP_3-B12)") (class "Default")
      (node (ref "CHIP_3") (pin "P50") (pinfunction "B12_P50") (pintype "bidirectional"))
      (node (ref "D94") (pin "4") (pinfunction "BLUE_CATHODE_4") (pintype "bidirectional"))
    )
    (net (code "118") (name "Net-(CHIP_3-B13)") (class "Default")
      (node (ref "CHIP_3") (pin "P44") (pinfunction "B13_P44") (pintype "bidirectional"))
      (node (ref "D93") (pin "4") (pinfunction "BLUE_CATHODE_4") (pintype "bidirectional"))
    )
    (net (code "119") (name "Net-(CHIP_3-B14)") (class "Default")
      (node (ref "CHIP_3") (pin "P41") (pinfunction "B14_P41") (pintype "bidirectional"))
      (node (ref "D81") (pin "4") (pinfunction "BLUE_CATHODE_4") (pintype "bidirectional"))
    )
    (net (code "120") (name "Net-(CHIP_3-B15)") (class "Default")
      (node (ref "CHIP_3") (pin "P35") (pinfunction "B15_P35") (pintype "bidirectional"))
      (node (ref "D89") (pin "4") (pinfunction "BLUE_CATHODE_4") (pintype "bidirectional"))
    )
    (net (code "121") (name "Net-(CHIP_3-G0)") (class "Default")
      (node (ref "CHIP_3") (pin "P9") (pinfunction "G0_P9") (pintype "bidirectional"))
      (node (ref "D90") (pin "1") (pinfunction "GREEN_CATHODE_1") (pintype "bidirectional"))
    )
    (net (code "122") (name "Net-(CHIP_3-G1)") (class "Default")
      (node (ref "CHIP_3") (pin "P15") (pinfunction "G1_P15") (pintype "bidirectional"))
      (node (ref "D91") (pin "1") (pinfunction "GREEN_CATHODE_1") (pintype "bidirectional"))
    )
    (net (code "123") (name "Net-(CHIP_3-G2)") (class "Default")
      (node (ref "CHIP_3") (pin "P18") (pinfunction "G2_P18") (pintype "bidirectional"))
      (node (ref "D87") (pin "1") (pinfunction "GREEN_CATHODE_1") (pintype "bidirectional"))
    )
    (net (code "124") (name "Net-(CHIP_3-G3)") (class "Default")
      (node (ref "CHIP_3") (pin "P24") (pinfunction "G3_P24") (pintype "bidirectional"))
      (node (ref "D95") (pin "1") (pinfunction "GREEN_CATHODE_1") (pintype "bidirectional"))
    )
    (net (code "125") (name "Net-(CHIP_3-G4)") (class "Default")
      (node (ref "CHIP_3") (pin "P6") (pinfunction "G4_P6") (pintype "bidirectional"))
      (node (ref "D96") (pin "1") (pinfunction "GREEN_CATHODE_1") (pintype "bidirectional"))
    )
    (net (code "126") (name "Net-(CHIP_3-G5)") (class "Default")
      (node (ref "CHIP_3") (pin "P12") (pinfunction "G5_P12") (pintype "bidirectional"))
      (node (ref "D88") (pin "1") (pinfunction "GREEN_CATHODE_1") (pintype "bidirectional"))
    )
    (net (code "127") (name "Net-(CHIP_3-G6)") (class "Default")
      (node (ref "CHIP_3") (pin "P21") (pinfunction "G6_P21") (pintype "bidirectional"))
      (node (ref "D83") (pin "1") (pinfunction "GREEN_CATHODE_1") (pintype "bidirectional"))
    )
    (net (code "128") (name "Net-(CHIP_3-G7)") (class "Default")
      (node (ref "CHIP_3") (pin "P27") (pinfunction "G7_P27") (pintype "bidirectional"))
      (node (ref "D92") (pin "1") (pinfunction "GREEN_CATHODE_1") (pintype "bidirectional"))
    )
    (net (code "129") (name "Net-(CHIP_3-G8)") (class "Default")
      (node (ref "CHIP_3") (pin "P51") (pinfunction "G8_P51") (pintype "bidirectional"))
      (node (ref "D85") (pin "1") (pinfunction "GREEN_CATHODE_1") (pintype "bidirectional"))
    )
    (net (code "130") (name "Net-(CHIP_3-G9)") (class "Default")
      (node (ref "CHIP_3") (pin "P45") (pinfunction "G9_P45") (pintype "bidirectional"))
      (node (ref "D86") (pin "1") (pinfunction "GREEN_CATHODE_1") (pintype "bidirectional"))
    )
    (net (code "131") (name "Net-(CHIP_3-G10)") (class "Default")
      (node (ref "CHIP_3") (pin "P36") (pinfunction "G10_P36") (pintype "bidirectional"))
      (node (ref "D82") (pin "1") (pinfunction "GREEN_CATHODE_1") (pintype "bidirectional"))
    )
    (net (code "132") (name "Net-(CHIP_3-G11)") (class "Default")
      (node (ref "CHIP_3") (pin "P30") (pinfunction "G11_P30") (pintype "bidirectional"))
      (node (ref "D84") (pin "1") (pinfunction "GREEN_CATHODE_1") (pintype "bidirectional"))
    )
    (net (code "133") (name "Net-(CHIP_3-G12)") (class "Default")
      (node (ref "CHIP_3") (pin "P48") (pinfunction "G12_P48") (pintype "bidirectional"))
      (node (ref "D94") (pin "1") (pinfunction "GREEN_CATHODE_1") (pintype "bidirectional"))
    )
    (net (code "134") (name "Net-(CHIP_3-G13)") (class "Default")
      (node (ref "CHIP_3") (pin "P42") (pinfunction "G13_P42") (pintype "bidirectional"))
      (node (ref "D93") (pin "1") (pinfunction "GREEN_CATHODE_1") (pintype "bidirectional"))
    )
    (net (code "135") (name "Net-(CHIP_3-G14)") (class "Default")
      (node (ref "CHIP_3") (pin "P39") (pinfunction "G14_P39") (pintype "bidirectional"))
      (node (ref "D81") (pin "1") (pinfunction "GREEN_CATHODE_1") (pintype "bidirectional"))
    )
    (net (code "136") (name "Net-(CHIP_3-G15)") (class "Default")
      (node (ref "CHIP_3") (pin "P33") (pinfunction "G15_P33") (pintype "bidirectional"))
      (node (ref "D89") (pin "1") (pinfunction "GREEN_CATHODE_1") (pintype "bidirectional"))
    )
    (net (code "137") (name "Net-(CHIP_3-R0)") (class "Default")
      (node (ref "CHIP_3") (pin "P8") (pinfunction "R0_P8") (pintype "bidirectional"))
      (node (ref "D90") (pin "3") (pinfunction "RED_CATHODE_3") (pintype "bidirectional"))
    )
    (net (code "138") (name "Net-(CHIP_3-R1)") (class "Default")
      (node (ref "CHIP_3") (pin "P14") (pinfunction "R1_P14") (pintype "bidirectional"))
      (node (ref "D91") (pin "3") (pinfunction "RED_CATHODE_3") (pintype "bidirectional"))
    )
    (net (code "139") (name "Net-(CHIP_3-R2)") (class "Default")
      (node (ref "CHIP_3") (pin "P17") (pinfunction "R2_P17") (pintype "bidirectional"))
      (node (ref "D87") (pin "3") (pinfunction "RED_CATHODE_3") (pintype "bidirectional"))
    )
    (net (code "140") (name "Net-(CHIP_3-R3)") (class "Default")
      (node (ref "CHIP_3") (pin "P23") (pinfunction "R3_P23") (pintype "bidirectional"))
      (node (ref "D95") (pin "3") (pinfunction "RED_CATHODE_3") (pintype "bidirectional"))
    )
    (net (code "141") (name "Net-(CHIP_3-R4)") (class "Default")
      (node (ref "CHIP_3") (pin "P5") (pinfunction "R4_P5") (pintype "bidirectional"))
      (node (ref "D96") (pin "3") (pinfunction "RED_CATHODE_3") (pintype "bidirectional"))
    )
    (net (code "142") (name "Net-(CHIP_3-R5)") (class "Default")
      (node (ref "CHIP_3") (pin "P11") (pinfunction "R5_P11") (pintype "bidirectional"))
      (node (ref "D88") (pin "3") (pinfunction "RED_CATHODE_3") (pintype "bidirectional"))
    )
    (net (code "143") (name "Net-(CHIP_3-R6)") (class "Default")
      (node (ref "CHIP_3") (pin "P20") (pinfunction "R6_P20") (pintype "bidirectional"))
      (node (ref "D83") (pin "3") (pinfunction "RED_CATHODE_3") (pintype "bidirectional"))
    )
    (net (code "144") (name "Net-(CHIP_3-R7)") (class "Default")
      (node (ref "CHIP_3") (pin "P26") (pinfunction "R7_P26") (pintype "bidirectional"))
      (node (ref "D92") (pin "3") (pinfunction "RED_CATHODE_3") (pintype "bidirectional"))
    )
    (net (code "145") (name "Net-(CHIP_3-R8)") (class "Default")
      (node (ref "CHIP_3") (pin "P52") (pinfunction "R8_P52") (pintype "bidirectional"))
      (node (ref "D85") (pin "3") (pinfunction "RED_CATHODE_3") (pintype "bidirectional"))
    )
    (net (code "146") (name "Net-(CHIP_3-R9)") (class "Default")
      (node (ref "CHIP_3") (pin "P46") (pinfunction "R9_P46") (pintype "bidirectional"))
      (node (ref "D86") (pin "3") (pinfunction "RED_CATHODE_3") (pintype "bidirectional"))
    )
    (net (code "147") (name "Net-(CHIP_3-R10)") (class "Default")
      (node (ref "CHIP_3") (pin "P37") (pinfunction "R10_P37") (pintype "bidirectional"))
      (node (ref "D82") (pin "3") (pinfunction "RED_CATHODE_3") (pintype "bidirectional"))
    )
    (net (code "148") (name "Net-(CHIP_3-R11)") (class "Default")
      (node (ref "CHIP_3") (pin "P31") (pinfunction "R11_P31") (pintype "bidirectional"))
      (node (ref "D84") (pin "3") (pinfunction "RED_CATHODE_3") (pintype "bidirectional"))
    )
    (net (code "149") (name "Net-(CHIP_3-R12)") (class "Default")
      (node (ref "CHIP_3") (pin "P49") (pinfunction "R12_P49") (pintype "bidirectional"))
      (node (ref "D94") (pin "3") (pinfunction "RED_CATHODE_3") (pintype "bidirectional"))
    )
    (net (code "150") (name "Net-(CHIP_3-R13)") (class "Default")
      (node (ref "CHIP_3") (pin "P43") (pinfunction "R13_P43") (pintype "bidirectional"))
      (node (ref "D93") (pin "3") (pinfunction "RED_CATHODE_3") (pintype "bidirectional"))
    )
    (net (code "151") (name "Net-(CHIP_3-R14)") (class "Default")
      (node (ref "CHIP_3") (pin "P40") (pinfunction "R14_P40") (pintype "bidirectional"))
      (node (ref "D81") (pin "3") (pinfunction "RED_CATHODE_3") (pintype "bidirectional"))
    )
    (net (code "152") (name "Net-(CHIP_3-R15)") (class "Default")
      (node (ref "CHIP_3") (pin "P34") (pinfunction "R15_P34") (pintype "bidirectional"))
      (node (ref "D89") (pin "3") (pinfunction "RED_CATHODE_3") (pintype "bidirectional"))
    )
    (net (code "153") (name "Net-(CHIP_3-SOUT)") (class "Default")
      (node (ref "CHIP_3") (pin "P28") (pinfunction "SOUT_P28") (pintype "bidirectional"))
      (node (ref "CHIP_4") (pin "P1") (pinfunction "SIN_P1") (pintype "bidirectional"))
      (node (ref "SOUT3") (pin "1") (pinfunction "1_1") (pintype "passive"))
    )
    (net (code "154") (name "Net-(CHIP_4-B0)") (class "Default")
      (node (ref "CHIP_4") (pin "P7") (pinfunction "B0_P7") (pintype "bidirectional"))
      (node (ref "D26") (pin "4") (pinfunction "BLUE_CATHODE_4") (pintype "bidirectional"))
    )
    (net (code "155") (name "Net-(CHIP_4-B1)") (class "Default")
      (node (ref "CHIP_4") (pin "P13") (pinfunction "B1_P13") (pintype "bidirectional"))
      (node (ref "D27") (pin "4") (pinfunction "BLUE_CATHODE_4") (pintype "bidirectional"))
    )
    (net (code "156") (name "Net-(CHIP_4-B2)") (class "Default")
      (node (ref "CHIP_4") (pin "P16") (pinfunction "B2_P16") (pintype "bidirectional"))
      (node (ref "D23") (pin "4") (pinfunction "BLUE_CATHODE_4") (pintype "bidirectional"))
    )
    (net (code "157") (name "Net-(CHIP_4-B3)") (class "Default")
      (node (ref "CHIP_4") (pin "P22") (pinfunction "B3_P22") (pintype "bidirectional"))
      (node (ref "D31") (pin "4") (pinfunction "BLUE_CATHODE_4") (pintype "bidirectional"))
    )
    (net (code "158") (name "Net-(CHIP_4-B4)") (class "Default")
      (node (ref "CHIP_4") (pin "P4") (pinfunction "B4_P4") (pintype "bidirectional"))
      (node (ref "D32") (pin "4") (pinfunction "BLUE_CATHODE_4") (pintype "bidirectional"))
    )
    (net (code "159") (name "Net-(CHIP_4-B5)") (class "Default")
      (node (ref "CHIP_4") (pin "P10") (pinfunction "B5_P10") (pintype "bidirectional"))
      (node (ref "D24") (pin "4") (pinfunction "BLUE_CATHODE_4") (pintype "bidirectional"))
    )
    (net (code "160") (name "Net-(CHIP_4-B6)") (class "Default")
      (node (ref "CHIP_4") (pin "P19") (pinfunction "B6_P19") (pintype "bidirectional"))
      (node (ref "D19") (pin "4") (pinfunction "BLUE_CATHODE_4") (pintype "bidirectional"))
    )
    (net (code "161") (name "Net-(CHIP_4-B7)") (class "Default")
      (node (ref "CHIP_4") (pin "P25") (pinfunction "B7_P25") (pintype "bidirectional"))
      (node (ref "D28") (pin "4") (pinfunction "BLUE_CATHODE_4") (pintype "bidirectional"))
    )
    (net (code "162") (name "Net-(CHIP_4-B8)") (class "Default")
      (node (ref "CHIP_4") (pin "P53") (pinfunction "B8_P53") (pintype "bidirectional"))
      (node (ref "D21") (pin "4") (pinfunction "BLUE_CATHODE_4") (pintype "bidirectional"))
    )
    (net (code "163") (name "Net-(CHIP_4-B9)") (class "Default")
      (node (ref "CHIP_4") (pin "P47") (pinfunction "B9_P47") (pintype "bidirectional"))
      (node (ref "D22") (pin "4") (pinfunction "BLUE_CATHODE_4") (pintype "bidirectional"))
    )
    (net (code "164") (name "Net-(CHIP_4-B10)") (class "Default")
      (node (ref "CHIP_4") (pin "P38") (pinfunction "B10_P38") (pintype "bidirectional"))
      (node (ref "D18") (pin "4") (pinfunction "BLUE_CATHODE_4") (pintype "bidirectional"))
    )
    (net (code "165") (name "Net-(CHIP_4-B11)") (class "Default")
      (node (ref "CHIP_4") (pin "P32") (pinfunction "B11_P32") (pintype "bidirectional"))
      (node (ref "D20") (pin "4") (pinfunction "BLUE_CATHODE_4") (pintype "bidirectional"))
    )
    (net (code "166") (name "Net-(CHIP_4-B12)") (class "Default")
      (node (ref "CHIP_4") (pin "P50") (pinfunction "B12_P50") (pintype "bidirectional"))
      (node (ref "D30") (pin "4") (pinfunction "BLUE_CATHODE_4") (pintype "bidirectional"))
    )
    (net (code "167") (name "Net-(CHIP_4-B13)") (class "Default")
      (node (ref "CHIP_4") (pin "P44") (pinfunction "B13_P44") (pintype "bidirectional"))
      (node (ref "D29") (pin "4") (pinfunction "BLUE_CATHODE_4") (pintype "bidirectional"))
    )
    (net (code "168") (name "Net-(CHIP_4-B14)") (class "Default")
      (node (ref "CHIP_4") (pin "P41") (pinfunction "B14_P41") (pintype "bidirectional"))
      (node (ref "D17") (pin "4") (pinfunction "BLUE_CATHODE_4") (pintype "bidirectional"))
    )
    (net (code "169") (name "Net-(CHIP_4-B15)") (class "Default")
      (node (ref "CHIP_4") (pin "P35") (pinfunction "B15_P35") (pintype "bidirectional"))
      (node (ref "D25") (pin "4") (pinfunction "BLUE_CATHODE_4") (pintype "bidirectional"))
    )
    (net (code "170") (name "Net-(CHIP_4-G0)") (class "Default")
      (node (ref "CHIP_4") (pin "P9") (pinfunction "G0_P9") (pintype "bidirectional"))
      (node (ref "D26") (pin "1") (pinfunction "GREEN_CATHODE_1") (pintype "bidirectional"))
    )
    (net (code "171") (name "Net-(CHIP_4-G1)") (class "Default")
      (node (ref "CHIP_4") (pin "P15") (pinfunction "G1_P15") (pintype "bidirectional"))
      (node (ref "D27") (pin "1") (pinfunction "GREEN_CATHODE_1") (pintype "bidirectional"))
    )
    (net (code "172") (name "Net-(CHIP_4-G2)") (class "Default")
      (node (ref "CHIP_4") (pin "P18") (pinfunction "G2_P18") (pintype "bidirectional"))
      (node (ref "D23") (pin "1") (pinfunction "GREEN_CATHODE_1") (pintype "bidirectional"))
    )
    (net (code "173") (name "Net-(CHIP_4-G3)") (class "Default")
      (node (ref "CHIP_4") (pin "P24") (pinfunction "G3_P24") (pintype "bidirectional"))
      (node (ref "D31") (pin "1") (pinfunction "GREEN_CATHODE_1") (pintype "bidirectional"))
    )
    (net (code "174") (name "Net-(CHIP_4-G4)") (class "Default")
      (node (ref "CHIP_4") (pin "P6") (pinfunction "G4_P6") (pintype "bidirectional"))
      (node (ref "D32") (pin "1") (pinfunction "GREEN_CATHODE_1") (pintype "bidirectional"))
    )
    (net (code "175") (name "Net-(CHIP_4-G5)") (class "Default")
      (node (ref "CHIP_4") (pin "P12") (pinfunction "G5_P12") (pintype "bidirectional"))
      (node (ref "D24") (pin "1") (pinfunction "GREEN_CATHODE_1") (pintype "bidirectional"))
    )
    (net (code "176") (name "Net-(CHIP_4-G6)") (class "Default")
      (node (ref "CHIP_4") (pin "P21") (pinfunction "G6_P21") (pintype "bidirectional"))
      (node (ref "D19") (pin "1") (pinfunction "GREEN_CATHODE_1") (pintype "bidirectional"))
    )
    (net (code "177") (name "Net-(CHIP_4-G7)") (class "Default")
      (node (ref "CHIP_4") (pin "P27") (pinfunction "G7_P27") (pintype "bidirectional"))
      (node (ref "D28") (pin "1") (pinfunction "GREEN_CATHODE_1") (pintype "bidirectional"))
    )
    (net (code "178") (name "Net-(CHIP_4-G8)") (class "Default")
      (node (ref "CHIP_4") (pin "P51") (pinfunction "G8_P51") (pintype "bidirectional"))
      (node (ref "D21") (pin "1") (pinfunction "GREEN_CATHODE_1") (pintype "bidirectional"))
    )
    (net (code "179") (name "Net-(CHIP_4-G9)") (class "Default")
      (node (ref "CHIP_4") (pin "P45") (pinfunction "G9_P45") (pintype "bidirectional"))
      (node (ref "D22") (pin "1") (pinfunction "GREEN_CATHODE_1") (pintype "bidirectional"))
    )
    (net (code "180") (name "Net-(CHIP_4-G10)") (class "Default")
      (node (ref "CHIP_4") (pin "P36") (pinfunction "G10_P36") (pintype "bidirectional"))
      (node (ref "D18") (pin "1") (pinfunction "GREEN_CATHODE_1") (pintype "bidirectional"))
    )
    (net (code "181") (name "Net-(CHIP_4-G11)") (class "Default")
      (node (ref "CHIP_4") (pin "P30") (pinfunction "G11_P30") (pintype "bidirectional"))
      (node (ref "D20") (pin "1") (pinfunction "GREEN_CATHODE_1") (pintype "bidirectional"))
    )
    (net (code "182") (name "Net-(CHIP_4-G12)") (class "Default")
      (node (ref "CHIP_4") (pin "P48") (pinfunction "G12_P48") (pintype "bidirectional"))
      (node (ref "D30") (pin "1") (pinfunction "GREEN_CATHODE_1") (pintype "bidirectional"))
    )
    (net (code "183") (name "Net-(CHIP_4-G13)") (class "Default")
      (node (ref "CHIP_4") (pin "P42") (pinfunction "G13_P42") (pintype "bidirectional"))
      (node (ref "D29") (pin "1") (pinfunction "GREEN_CATHODE_1") (pintype "bidirectional"))
    )
    (net (code "184") (name "Net-(CHIP_4-G14)") (class "Default")
      (node (ref "CHIP_4") (pin "P39") (pinfunction "G14_P39") (pintype "bidirectional"))
      (node (ref "D17") (pin "1") (pinfunction "GREEN_CATHODE_1") (pintype "bidirectional"))
    )
    (net (code "185") (name "Net-(CHIP_4-G15)") (class "Default")
      (node (ref "CHIP_4") (pin "P33") (pinfunction "G15_P33") (pintype "bidirectional"))
      (node (ref "D25") (pin "1") (pinfunction "GREEN_CATHODE_1") (pintype "bidirectional"))
    )
    (net (code "186") (name "Net-(CHIP_4-R0)") (class "Default")
      (node (ref "CHIP_4") (pin "P8") (pinfunction "R0_P8") (pintype "bidirectional"))
      (node (ref "D26") (pin "3") (pinfunction "RED_CATHODE_3") (pintype "bidirectional"))
    )
    (net (code "187") (name "Net-(CHIP_4-R1)") (class "Default")
      (node (ref "CHIP_4") (pin "P14") (pinfunction "R1_P14") (pintype "bidirectional"))
      (node (ref "D27") (pin "3") (pinfunction "RED_CATHODE_3") (pintype "bidirectional"))
    )
    (net (code "188") (name "Net-(CHIP_4-R2)") (class "Default")
      (node (ref "CHIP_4") (pin "P17") (pinfunction "R2_P17") (pintype "bidirectional"))
      (node (ref "D23") (pin "3") (pinfunction "RED_CATHODE_3") (pintype "bidirectional"))
    )
    (net (code "189") (name "Net-(CHIP_4-R3)") (class "Default")
      (node (ref "CHIP_4") (pin "P23") (pinfunction "R3_P23") (pintype "bidirectional"))
      (node (ref "D31") (pin "3") (pinfunction "RED_CATHODE_3") (pintype "bidirectional"))
    )
    (net (code "190") (name "Net-(CHIP_4-R4)") (class "Default")
      (node (ref "CHIP_4") (pin "P5") (pinfunction "R4_P5") (pintype "bidirectional"))
      (node (ref "D32") (pin "3") (pinfunction "RED_CATHODE_3") (pintype "bidirectional"))
    )
    (net (code "191") (name "Net-(CHIP_4-R5)") (class "Default")
      (node (ref "CHIP_4") (pin "P11") (pinfunction "R5_P11") (pintype "bidirectional"))
      (node (ref "D24") (pin "3") (pinfunction "RED_CATHODE_3") (pintype "bidirectional"))
    )
    (net (code "192") (name "Net-(CHIP_4-R6)") (class "Default")
      (node (ref "CHIP_4") (pin "P20") (pinfunction "R6_P20") (pintype "bidirectional"))
      (node (ref "D19") (pin "3") (pinfunction "RED_CATHODE_3") (pintype "bidirectional"))
    )
    (net (code "193") (name "Net-(CHIP_4-R7)") (class "Default")
      (node (ref "CHIP_4") (pin "P26") (pinfunction "R7_P26") (pintype "bidirectional"))
      (node (ref "D28") (pin "3") (pinfunction "RED_CATHODE_3") (pintype "bidirectional"))
    )
    (net (code "194") (name "Net-(CHIP_4-R8)") (class "Default")
      (node (ref "CHIP_4") (pin "P52") (pinfunction "R8_P52") (pintype "bidirectional"))
      (node (ref "D21") (pin "3") (pinfunction "RED_CATHODE_3") (pintype "bidirectional"))
    )
    (net (code "195") (name "Net-(CHIP_4-R9)") (class "Default")
      (node (ref "CHIP_4") (pin "P46") (pinfunction "R9_P46") (pintype "bidirectional"))
      (node (ref "D22") (pin "3") (pinfunction "RED_CATHODE_3") (pintype "bidirectional"))
    )
    (net (code "196") (name "Net-(CHIP_4-R10)") (class "Default")
      (node (ref "CHIP_4") (pin "P37") (pinfunction "R10_P37") (pintype "bidirectional"))
      (node (ref "D18") (pin "3") (pinfunction "RED_CATHODE_3") (pintype "bidirectional"))
    )
    (net (code "197") (name "Net-(CHIP_4-R11)") (class "Default")
      (node (ref "CHIP_4") (pin "P31") (pinfunction "R11_P31") (pintype "bidirectional"))
      (node (ref "D20") (pin "3") (pinfunction "RED_CATHODE_3") (pintype "bidirectional"))
    )
    (net (code "198") (name "Net-(CHIP_4-R12)") (class "Default")
      (node (ref "CHIP_4") (pin "P49") (pinfunction "R12_P49") (pintype "bidirectional"))
      (node (ref "D30") (pin "3") (pinfunction "RED_CATHODE_3") (pintype "bidirectional"))
    )
    (net (code "199") (name "Net-(CHIP_4-R13)") (class "Default")
      (node (ref "CHIP_4") (pin "P43") (pinfunction "R13_P43") (pintype "bidirectional"))
      (node (ref "D29") (pin "3") (pinfunction "RED_CATHODE_3") (pintype "bidirectional"))
    )
    (net (code "200") (name "Net-(CHIP_4-R14)") (class "Default")
      (node (ref "CHIP_4") (pin "P40") (pinfunction "R14_P40") (pintype "bidirectional"))
      (node (ref "D17") (pin "3") (pinfunction "RED_CATHODE_3") (pintype "bidirectional"))
    )
    (net (code "201") (name "Net-(CHIP_4-R15)") (class "Default")
      (node (ref "CHIP_4") (pin "P34") (pinfunction "R15_P34") (pintype "bidirectional"))
      (node (ref "D25") (pin "3") (pinfunction "RED_CATHODE_3") (pintype "bidirectional"))
    )
    (net (code "202") (name "Net-(CHIP_4-SOUT)") (class "Default")
      (node (ref "CHIP_4") (pin "P28") (pinfunction "SOUT_P28") (pintype "bidirectional"))
      (node (ref "CHIP_5") (pin "P1") (pinfunction "SIN_P1") (pintype "bidirectional"))
      (node (ref "SOUT4") (pin "1") (pinfunction "1_1") (pintype "passive"))
    )
    (net (code "203") (name "Net-(CHIP_5-B0)") (class "Default")
      (node (ref "CHIP_5") (pin "P7") (pinfunction "B0_P7") (pintype "bidirectional"))
      (node (ref "D42") (pin "4") (pinfunction "BLUE_CATHODE_4") (pintype "bidirectional"))
    )
    (net (code "204") (name "Net-(CHIP_5-B1)") (class "Default")
      (node (ref "CHIP_5") (pin "P13") (pinfunction "B1_P13") (pintype "bidirectional"))
      (node (ref "D43") (pin "4") (pinfunction "BLUE_CATHODE_4") (pintype "bidirectional"))
    )
    (net (code "205") (name "Net-(CHIP_5-B2)") (class "Default")
      (node (ref "CHIP_5") (pin "P16") (pinfunction "B2_P16") (pintype "bidirectional"))
      (node (ref "D39") (pin "4") (pinfunction "BLUE_CATHODE_4") (pintype "bidirectional"))
    )
    (net (code "206") (name "Net-(CHIP_5-B3)") (class "Default")
      (node (ref "CHIP_5") (pin "P22") (pinfunction "B3_P22") (pintype "bidirectional"))
      (node (ref "D47") (pin "4") (pinfunction "BLUE_CATHODE_4") (pintype "bidirectional"))
    )
    (net (code "207") (name "Net-(CHIP_5-B4)") (class "Default")
      (node (ref "CHIP_5") (pin "P4") (pinfunction "B4_P4") (pintype "bidirectional"))
      (node (ref "D48") (pin "4") (pinfunction "BLUE_CATHODE_4") (pintype "bidirectional"))
    )
    (net (code "208") (name "Net-(CHIP_5-B5)") (class "Default")
      (node (ref "CHIP_5") (pin "P10") (pinfunction "B5_P10") (pintype "bidirectional"))
      (node (ref "D40") (pin "4") (pinfunction "BLUE_CATHODE_4") (pintype "bidirectional"))
    )
    (net (code "209") (name "Net-(CHIP_5-B6)") (class "Default")
      (node (ref "CHIP_5") (pin "P19") (pinfunction "B6_P19") (pintype "bidirectional"))
      (node (ref "D35") (pin "4") (pinfunction "BLUE_CATHODE_4") (pintype "bidirectional"))
    )
    (net (code "210") (name "Net-(CHIP_5-B7)") (class "Default")
      (node (ref "CHIP_5") (pin "P25") (pinfunction "B7_P25") (pintype "bidirectional"))
      (node (ref "D44") (pin "4") (pinfunction "BLUE_CATHODE_4") (pintype "bidirectional"))
    )
    (net (code "211") (name "Net-(CHIP_5-B8)") (class "Default")
      (node (ref "CHIP_5") (pin "P53") (pinfunction "B8_P53") (pintype "bidirectional"))
      (node (ref "D37") (pin "4") (pinfunction "BLUE_CATHODE_4") (pintype "bidirectional"))
    )
    (net (code "212") (name "Net-(CHIP_5-B9)") (class "Default")
      (node (ref "CHIP_5") (pin "P47") (pinfunction "B9_P47") (pintype "bidirectional"))
      (node (ref "D38") (pin "4") (pinfunction "BLUE_CATHODE_4") (pintype "bidirectional"))
    )
    (net (code "213") (name "Net-(CHIP_5-B10)") (class "Default")
      (node (ref "CHIP_5") (pin "P38") (pinfunction "B10_P38") (pintype "bidirectional"))
      (node (ref "D34") (pin "4") (pinfunction "BLUE_CATHODE_4") (pintype "bidirectional"))
    )
    (net (code "214") (name "Net-(CHIP_5-B11)") (class "Default")
      (node (ref "CHIP_5") (pin "P32") (pinfunction "B11_P32") (pintype "bidirectional"))
      (node (ref "D36") (pin "4") (pinfunction "BLUE_CATHODE_4") (pintype "bidirectional"))
    )
    (net (code "215") (name "Net-(CHIP_5-B12)") (class "Default")
      (node (ref "CHIP_5") (pin "P50") (pinfunction "B12_P50") (pintype "bidirectional"))
      (node (ref "D46") (pin "4") (pinfunction "BLUE_CATHODE_4") (pintype "bidirectional"))
    )
    (net (code "216") (name "Net-(CHIP_5-B13)") (class "Default")
      (node (ref "CHIP_5") (pin "P44") (pinfunction "B13_P44") (pintype "bidirectional"))
      (node (ref "D45") (pin "4") (pinfunction "BLUE_CATHODE_4") (pintype "bidirectional"))
    )
    (net (code "217") (name "Net-(CHIP_5-B14)") (class "Default")
      (node (ref "CHIP_5") (pin "P41") (pinfunction "B14_P41") (pintype "bidirectional"))
      (node (ref "D33") (pin "4") (pinfunction "BLUE_CATHODE_4") (pintype "bidirectional"))
    )
    (net (code "218") (name "Net-(CHIP_5-B15)") (class "Default")
      (node (ref "CHIP_5") (pin "P35") (pinfunction "B15_P35") (pintype "bidirectional"))
      (node (ref "D41") (pin "4") (pinfunction "BLUE_CATHODE_4") (pintype "bidirectional"))
    )
    (net (code "219") (name "Net-(CHIP_5-G0)") (class "Default")
      (node (ref "CHIP_5") (pin "P9") (pinfunction "G0_P9") (pintype "bidirectional"))
      (node (ref "D42") (pin "1") (pinfunction "GREEN_CATHODE_1") (pintype "bidirectional"))
    )
    (net (code "220") (name "Net-(CHIP_5-G1)") (class "Default")
      (node (ref "CHIP_5") (pin "P15") (pinfunction "G1_P15") (pintype "bidirectional"))
      (node (ref "D43") (pin "1") (pinfunction "GREEN_CATHODE_1") (pintype "bidirectional"))
    )
    (net (code "221") (name "Net-(CHIP_5-G2)") (class "Default")
      (node (ref "CHIP_5") (pin "P18") (pinfunction "G2_P18") (pintype "bidirectional"))
      (node (ref "D39") (pin "1") (pinfunction "GREEN_CATHODE_1") (pintype "bidirectional"))
    )
    (net (code "222") (name "Net-(CHIP_5-G3)") (class "Default")
      (node (ref "CHIP_5") (pin "P24") (pinfunction "G3_P24") (pintype "bidirectional"))
      (node (ref "D47") (pin "1") (pinfunction "GREEN_CATHODE_1") (pintype "bidirectional"))
    )
    (net (code "223") (name "Net-(CHIP_5-G4)") (class "Default")
      (node (ref "CHIP_5") (pin "P6") (pinfunction "G4_P6") (pintype "bidirectional"))
      (node (ref "D48") (pin "1") (pinfunction "GREEN_CATHODE_1") (pintype "bidirectional"))
    )
    (net (code "224") (name "Net-(CHIP_5-G5)") (class "Default")
      (node (ref "CHIP_5") (pin "P12") (pinfunction "G5_P12") (pintype "bidirectional"))
      (node (ref "D40") (pin "1") (pinfunction "GREEN_CATHODE_1") (pintype "bidirectional"))
    )
    (net (code "225") (name "Net-(CHIP_5-G6)") (class "Default")
      (node (ref "CHIP_5") (pin "P21") (pinfunction "G6_P21") (pintype "bidirectional"))
      (node (ref "D35") (pin "1") (pinfunction "GREEN_CATHODE_1") (pintype "bidirectional"))
    )
    (net (code "226") (name "Net-(CHIP_5-G7)") (class "Default")
      (node (ref "CHIP_5") (pin "P27") (pinfunction "G7_P27") (pintype "bidirectional"))
      (node (ref "D44") (pin "1") (pinfunction "GREEN_CATHODE_1") (pintype "bidirectional"))
    )
    (net (code "227") (name "Net-(CHIP_5-G8)") (class "Default")
      (node (ref "CHIP_5") (pin "P51") (pinfunction "G8_P51") (pintype "bidirectional"))
      (node (ref "D37") (pin "1") (pinfunction "GREEN_CATHODE_1") (pintype "bidirectional"))
    )
    (net (code "228") (name "Net-(CHIP_5-G9)") (class "Default")
      (node (ref "CHIP_5") (pin "P45") (pinfunction "G9_P45") (pintype "bidirectional"))
      (node (ref "D38") (pin "1") (pinfunction "GREEN_CATHODE_1") (pintype "bidirectional"))
    )
    (net (code "229") (name "Net-(CHIP_5-G10)") (class "Default")
      (node (ref "CHIP_5") (pin "P36") (pinfunction "G10_P36") (pintype "bidirectional"))
      (node (ref "D34") (pin "1") (pinfunction "GREEN_CATHODE_1") (pintype "bidirectional"))
    )
    (net (code "230") (name "Net-(CHIP_5-G11)") (class "Default")
      (node (ref "CHIP_5") (pin "P30") (pinfunction "G11_P30") (pintype "bidirectional"))
      (node (ref "D36") (pin "1") (pinfunction "GREEN_CATHODE_1") (pintype "bidirectional"))
    )
    (net (code "231") (name "Net-(CHIP_5-G12)") (class "Default")
      (node (ref "CHIP_5") (pin "P48") (pinfunction "G12_P48") (pintype "bidirectional"))
      (node (ref "D46") (pin "1") (pinfunction "GREEN_CATHODE_1") (pintype "bidirectional"))
    )
    (net (code "232") (name "Net-(CHIP_5-G13)") (class "Default")
      (node (ref "CHIP_5") (pin "P42") (pinfunction "G13_P42") (pintype "bidirectional"))
      (node (ref "D45") (pin "1") (pinfunction "GREEN_CATHODE_1") (pintype "bidirectional"))
    )
    (net (code "233") (name "Net-(CHIP_5-G14)") (class "Default")
      (node (ref "CHIP_5") (pin "P39") (pinfunction "G14_P39") (pintype "bidirectional"))
      (node (ref "D33") (pin "1") (pinfunction "GREEN_CATHODE_1") (pintype "bidirectional"))
    )
    (net (code "234") (name "Net-(CHIP_5-G15)") (class "Default")
      (node (ref "CHIP_5") (pin "P33") (pinfunction "G15_P33") (pintype "bidirectional"))
      (node (ref "D41") (pin "1") (pinfunction "GREEN_CATHODE_1") (pintype "bidirectional"))
    )
    (net (code "235") (name "Net-(CHIP_5-R0)") (class "Default")
      (node (ref "CHIP_5") (pin "P8") (pinfunction "R0_P8") (pintype "bidirectional"))
      (node (ref "D42") (pin "3") (pinfunction "RED_CATHODE_3") (pintype "bidirectional"))
    )
    (net (code "236") (name "Net-(CHIP_5-R1)") (class "Default")
      (node (ref "CHIP_5") (pin "P14") (pinfunction "R1_P14") (pintype "bidirectional"))
      (node (ref "D43") (pin "3") (pinfunction "RED_CATHODE_3") (pintype "bidirectional"))
    )
    (net (code "237") (name "Net-(CHIP_5-R2)") (class "Default")
      (node (ref "CHIP_5") (pin "P17") (pinfunction "R2_P17") (pintype "bidirectional"))
      (node (ref "D39") (pin "3") (pinfunction "RED_CATHODE_3") (pintype "bidirectional"))
    )
    (net (code "238") (name "Net-(CHIP_5-R3)") (class "Default")
      (node (ref "CHIP_5") (pin "P23") (pinfunction "R3_P23") (pintype "bidirectional"))
      (node (ref "D47") (pin "3") (pinfunction "RED_CATHODE_3") (pintype "bidirectional"))
    )
    (net (code "239") (name "Net-(CHIP_5-R4)") (class "Default")
      (node (ref "CHIP_5") (pin "P5") (pinfunction "R4_P5") (pintype "bidirectional"))
      (node (ref "D48") (pin "3") (pinfunction "RED_CATHODE_3") (pintype "bidirectional"))
    )
    (net (code "240") (name "Net-(CHIP_5-R5)") (class "Default")
      (node (ref "CHIP_5") (pin "P11") (pinfunction "R5_P11") (pintype "bidirectional"))
      (node (ref "D40") (pin "3") (pinfunction "RED_CATHODE_3") (pintype "bidirectional"))
    )
    (net (code "241") (name "Net-(CHIP_5-R6)") (class "Default")
      (node (ref "CHIP_5") (pin "P20") (pinfunction "R6_P20") (pintype "bidirectional"))
      (node (ref "D35") (pin "3") (pinfunction "RED_CATHODE_3") (pintype "bidirectional"))
    )
    (net (code "242") (name "Net-(CHIP_5-R7)") (class "Default")
      (node (ref "CHIP_5") (pin "P26") (pinfunction "R7_P26") (pintype "bidirectional"))
      (node (ref "D44") (pin "3") (pinfunction "RED_CATHODE_3") (pintype "bidirectional"))
    )
    (net (code "243") (name "Net-(CHIP_5-R8)") (class "Default")
      (node (ref "CHIP_5") (pin "P52") (pinfunction "R8_P52") (pintype "bidirectional"))
      (node (ref "D37") (pin "3") (pinfunction "RED_CATHODE_3") (pintype "bidirectional"))
    )
    (net (code "244") (name "Net-(CHIP_5-R9)") (class "Default")
      (node (ref "CHIP_5") (pin "P46") (pinfunction "R9_P46") (pintype "bidirectional"))
      (node (ref "D38") (pin "3") (pinfunction "RED_CATHODE_3") (pintype "bidirectional"))
    )
    (net (code "245") (name "Net-(CHIP_5-R10)") (class "Default")
      (node (ref "CHIP_5") (pin "P37") (pinfunction "R10_P37") (pintype "bidirectional"))
      (node (ref "D34") (pin "3") (pinfunction "RED_CATHODE_3") (pintype "bidirectional"))
    )
    (net (code "246") (name "Net-(CHIP_5-R11)") (class "Default")
      (node (ref "CHIP_5") (pin "P31") (pinfunction "R11_P31") (pintype "bidirectional"))
      (node (ref "D36") (pin "3") (pinfunction "RED_CATHODE_3") (pintype "bidirectional"))
    )
    (net (code "247") (name "Net-(CHIP_5-R12)") (class "Default")
      (node (ref "CHIP_5") (pin "P49") (pinfunction "R12_P49") (pintype "bidirectional"))
      (node (ref "D46") (pin "3") (pinfunction "RED_CATHODE_3") (pintype "bidirectional"))
    )
    (net (code "248") (name "Net-(CHIP_5-R13)") (class "Default")
      (node (ref "CHIP_5") (pin "P43") (pinfunction "R13_P43") (pintype "bidirectional"))
      (node (ref "D45") (pin "3") (pinfunction "RED_CATHODE_3") (pintype "bidirectional"))
    )
    (net (code "249") (name "Net-(CHIP_5-R14)") (class "Default")
      (node (ref "CHIP_5") (pin "P40") (pinfunction "R14_P40") (pintype "bidirectional"))
      (node (ref "D33") (pin "3") (pinfunction "RED_CATHODE_3") (pintype "bidirectional"))
    )
    (net (code "250") (name "Net-(CHIP_5-R15)") (class "Default")
      (node (ref "CHIP_5") (pin "P34") (pinfunction "R15_P34") (pintype "bidirectional"))
      (node (ref "D41") (pin "3") (pinfunction "RED_CATHODE_3") (pintype "bidirectional"))
    )
    (net (code "251") (name "Net-(CHIP_5-SOUT)") (class "Default")
      (node (ref "CHIP_5") (pin "P28") (pinfunction "SOUT_P28") (pintype "bidirectional"))
      (node (ref "CHIP_6") (pin "P1") (pinfunction "SIN_P1") (pintype "bidirectional"))
      (node (ref "SOUT5") (pin "1") (pinfunction "1_1") (pintype "passive"))
    )
    (net (code "252") (name "Net-(CHIP_6-B0)") (class "Default")
      (node (ref "CHIP_6") (pin "P7") (pinfunction "B0_P7") (pintype "bidirectional"))
      (node (ref "D10") (pin "4") (pinfunction "BLUE_CATHODE_4") (pintype "bidirectional"))
    )
    (net (code "253") (name "Net-(CHIP_6-B1)") (class "Default")
      (node (ref "CHIP_6") (pin "P13") (pinfunction "B1_P13") (pintype "bidirectional"))
      (node (ref "D11") (pin "4") (pinfunction "BLUE_CATHODE_4") (pintype "bidirectional"))
    )
    (net (code "254") (name "Net-(CHIP_6-B2)") (class "Default")
      (node (ref "CHIP_6") (pin "P16") (pinfunction "B2_P16") (pintype "bidirectional"))
      (node (ref "D7") (pin "4") (pinfunction "BLUE_CATHODE_4") (pintype "bidirectional"))
    )
    (net (code "255") (name "Net-(CHIP_6-B3)") (class "Default")
      (node (ref "CHIP_6") (pin "P22") (pinfunction "B3_P22") (pintype "bidirectional"))
      (node (ref "D15") (pin "4") (pinfunction "BLUE_CATHODE_4") (pintype "bidirectional"))
    )
    (net (code "256") (name "Net-(CHIP_6-B4)") (class "Default")
      (node (ref "CHIP_6") (pin "P4") (pinfunction "B4_P4") (pintype "bidirectional"))
      (node (ref "D16") (pin "4") (pinfunction "BLUE_CATHODE_4") (pintype "bidirectional"))
    )
    (net (code "257") (name "Net-(CHIP_6-B5)") (class "Default")
      (node (ref "CHIP_6") (pin "P10") (pinfunction "B5_P10") (pintype "bidirectional"))
      (node (ref "D8") (pin "4") (pinfunction "BLUE_CATHODE_4") (pintype "bidirectional"))
    )
    (net (code "258") (name "Net-(CHIP_6-B6)") (class "Default")
      (node (ref "CHIP_6") (pin "P19") (pinfunction "B6_P19") (pintype "bidirectional"))
      (node (ref "D3") (pin "4") (pinfunction "BLUE_CATHODE_4") (pintype "bidirectional"))
    )
    (net (code "259") (name "Net-(CHIP_6-B7)") (class "Default")
      (node (ref "CHIP_6") (pin "P25") (pinfunction "B7_P25") (pintype "bidirectional"))
      (node (ref "D12") (pin "4") (pinfunction "BLUE_CATHODE_4") (pintype "bidirectional"))
    )
    (net (code "260") (name "Net-(CHIP_6-B8)") (class "Default")
      (node (ref "CHIP_6") (pin "P53") (pinfunction "B8_P53") (pintype "bidirectional"))
      (node (ref "D5") (pin "4") (pinfunction "BLUE_CATHODE_4") (pintype "bidirectional"))
    )
    (net (code "261") (name "Net-(CHIP_6-B9)") (class "Default")
      (node (ref "CHIP_6") (pin "P47") (pinfunction "B9_P47") (pintype "bidirectional"))
      (node (ref "D6") (pin "4") (pinfunction "BLUE_CATHODE_4") (pintype "bidirectional"))
    )
    (net (code "262") (name "Net-(CHIP_6-B10)") (class "Default")
      (node (ref "CHIP_6") (pin "P38") (pinfunction "B10_P38") (pintype "bidirectional"))
      (node (ref "D2") (pin "4") (pinfunction "BLUE_CATHODE_4") (pintype "bidirectional"))
    )
    (net (code "263") (name "Net-(CHIP_6-B11)") (class "Default")
      (node (ref "CHIP_6") (pin "P32") (pinfunction "B11_P32") (pintype "bidirectional"))
      (node (ref "D4") (pin "4") (pinfunction "BLUE_CATHODE_4") (pintype "bidirectional"))
    )
    (net (code "264") (name "Net-(CHIP_6-B12)") (class "Default")
      (node (ref "CHIP_6") (pin "P50") (pinfunction "B12_P50") (pintype "bidirectional"))
      (node (ref "D14") (pin "4") (pinfunction "BLUE_CATHODE_4") (pintype "bidirectional"))
    )
    (net (code "265") (name "Net-(CHIP_6-B13)") (class "Default")
      (node (ref "CHIP_6") (pin "P44") (pinfunction "B13_P44") (pintype "bidirectional"))
      (node (ref "D13") (pin "4") (pinfunction "BLUE_CATHODE_4") (pintype "bidirectional"))
    )
    (net (code "266") (name "Net-(CHIP_6-B14)") (class "Default")
      (node (ref "CHIP_6") (pin "P41") (pinfunction "B14_P41") (pintype "bidirectional"))
      (node (ref "D1") (pin "4") (pinfunction "BLUE_CATHODE_4") (pintype "bidirectional"))
    )
    (net (code "267") (name "Net-(CHIP_6-B15)") (class "Default")
      (node (ref "CHIP_6") (pin "P35") (pinfunction "B15_P35") (pintype "bidirectional"))
      (node (ref "D9") (pin "4") (pinfunction "BLUE_CATHODE_4") (pintype "bidirectional"))
    )
    (net (code "268") (name "Net-(CHIP_6-G0)") (class "Default")
      (node (ref "CHIP_6") (pin "P9") (pinfunction "G0_P9") (pintype "bidirectional"))
      (node (ref "D10") (pin "1") (pinfunction "GREEN_CATHODE_1") (pintype "bidirectional"))
    )
    (net (code "269") (name "Net-(CHIP_6-G1)") (class "Default")
      (node (ref "CHIP_6") (pin "P15") (pinfunction "G1_P15") (pintype "bidirectional"))
      (node (ref "D11") (pin "1") (pinfunction "GREEN_CATHODE_1") (pintype "bidirectional"))
    )
    (net (code "270") (name "Net-(CHIP_6-G2)") (class "Default")
      (node (ref "CHIP_6") (pin "P18") (pinfunction "G2_P18") (pintype "bidirectional"))
      (node (ref "D7") (pin "1") (pinfunction "GREEN_CATHODE_1") (pintype "bidirectional"))
    )
    (net (code "271") (name "Net-(CHIP_6-G3)") (class "Default")
      (node (ref "CHIP_6") (pin "P24") (pinfunction "G3_P24") (pintype "bidirectional"))
      (node (ref "D15") (pin "1") (pinfunction "GREEN_CATHODE_1") (pintype "bidirectional"))
    )
    (net (code "272") (name "Net-(CHIP_6-G4)") (class "Default")
      (node (ref "CHIP_6") (pin "P6") (pinfunction "G4_P6") (pintype "bidirectional"))
      (node (ref "D16") (pin "1") (pinfunction "GREEN_CATHODE_1") (pintype "bidirectional"))
    )
    (net (code "273") (name "Net-(CHIP_6-G5)") (class "Default")
      (node (ref "CHIP_6") (pin "P12") (pinfunction "G5_P12") (pintype "bidirectional"))
      (node (ref "D8") (pin "1") (pinfunction "GREEN_CATHODE_1") (pintype "bidirectional"))
    )
    (net (code "274") (name "Net-(CHIP_6-G6)") (class "Default")
      (node (ref "CHIP_6") (pin "P21") (pinfunction "G6_P21") (pintype "bidirectional"))
      (node (ref "D3") (pin "1") (pinfunction "GREEN_CATHODE_1") (pintype "bidirectional"))
    )
    (net (code "275") (name "Net-(CHIP_6-G7)") (class "Default")
      (node (ref "CHIP_6") (pin "P27") (pinfunction "G7_P27") (pintype "bidirectional"))
      (node (ref "D12") (pin "1") (pinfunction "GREEN_CATHODE_1") (pintype "bidirectional"))
    )
    (net (code "276") (name "Net-(CHIP_6-G8)") (class "Default")
      (node (ref "CHIP_6") (pin "P51") (pinfunction "G8_P51") (pintype "bidirectional"))
      (node (ref "D5") (pin "1") (pinfunction "GREEN_CATHODE_1") (pintype "bidirectional"))
    )
    (net (code "277") (name "Net-(CHIP_6-G9)") (class "Default")
      (node (ref "CHIP_6") (pin "P45") (pinfunction "G9_P45") (pintype "bidirectional"))
      (node (ref "D6") (pin "1") (pinfunction "GREEN_CATHODE_1") (pintype "bidirectional"))
    )
    (net (code "278") (name "Net-(CHIP_6-G10)") (class "Default")
      (node (ref "CHIP_6") (pin "P36") (pinfunction "G10_P36") (pintype "bidirectional"))
      (node (ref "D2") (pin "1") (pinfunction "GREEN_CATHODE_1") (pintype "bidirectional"))
    )
    (net (code "279") (name "Net-(CHIP_6-G11)") (class "Default")
      (node (ref "CHIP_6") (pin "P30") (pinfunction "G11_P30") (pintype "bidirectional"))
      (node (ref "D4") (pin "1") (pinfunction "GREEN_CATHODE_1") (pintype "bidirectional"))
    )
    (net (code "280") (name "Net-(CHIP_6-G12)") (class "Default")
      (node (ref "CHIP_6") (pin "P48") (pinfunction "G12_P48") (pintype "bidirectional"))
      (node (ref "D14") (pin "1") (pinfunction "GREEN_CATHODE_1") (pintype "bidirectional"))
    )
    (net (code "281") (name "Net-(CHIP_6-G13)") (class "Default")
      (node (ref "CHIP_6") (pin "P42") (pinfunction "G13_P42") (pintype "bidirectional"))
      (node (ref "D13") (pin "1") (pinfunction "GREEN_CATHODE_1") (pintype "bidirectional"))
    )
    (net (code "282") (name "Net-(CHIP_6-G14)") (class "Default")
      (node (ref "CHIP_6") (pin "P39") (pinfunction "G14_P39") (pintype "bidirectional"))
      (node (ref "D1") (pin "1") (pinfunction "GREEN_CATHODE_1") (pintype "bidirectional"))
    )
    (net (code "283") (name "Net-(CHIP_6-G15)") (class "Default")
      (node (ref "CHIP_6") (pin "P33") (pinfunction "G15_P33") (pintype "bidirectional"))
      (node (ref "D9") (pin "1") (pinfunction "GREEN_CATHODE_1") (pintype "bidirectional"))
    )
    (net (code "284") (name "Net-(CHIP_6-R0)") (class "Default")
      (node (ref "CHIP_6") (pin "P8") (pinfunction "R0_P8") (pintype "bidirectional"))
      (node (ref "D10") (pin "3") (pinfunction "RED_CATHODE_3") (pintype "bidirectional"))
    )
    (net (code "285") (name "Net-(CHIP_6-R1)") (class "Default")
      (node (ref "CHIP_6") (pin "P14") (pinfunction "R1_P14") (pintype "bidirectional"))
      (node (ref "D11") (pin "3") (pinfunction "RED_CATHODE_3") (pintype "bidirectional"))
    )
    (net (code "286") (name "Net-(CHIP_6-R2)") (class "Default")
      (node (ref "CHIP_6") (pin "P17") (pinfunction "R2_P17") (pintype "bidirectional"))
      (node (ref "D7") (pin "3") (pinfunction "RED_CATHODE_3") (pintype "bidirectional"))
    )
    (net (code "287") (name "Net-(CHIP_6-R3)") (class "Default")
      (node (ref "CHIP_6") (pin "P23") (pinfunction "R3_P23") (pintype "bidirectional"))
      (node (ref "D15") (pin "3") (pinfunction "RED_CATHODE_3") (pintype "bidirectional"))
    )
    (net (code "288") (name "Net-(CHIP_6-R4)") (class "Default")
      (node (ref "CHIP_6") (pin "P5") (pinfunction "R4_P5") (pintype "bidirectional"))
      (node (ref "D16") (pin "3") (pinfunction "RED_CATHODE_3") (pintype "bidirectional"))
    )
    (net (code "289") (name "Net-(CHIP_6-R5)") (class "Default")
      (node (ref "CHIP_6") (pin "P11") (pinfunction "R5_P11") (pintype "bidirectional"))
      (node (ref "D8") (pin "3") (pinfunction "RED_CATHODE_3") (pintype "bidirectional"))
    )
    (net (code "290") (name "Net-(CHIP_6-R6)") (class "Default")
      (node (ref "CHIP_6") (pin "P20") (pinfunction "R6_P20") (pintype "bidirectional"))
      (node (ref "D3") (pin "3") (pinfunction "RED_CATHODE_3") (pintype "bidirectional"))
    )
    (net (code "291") (name "Net-(CHIP_6-R7)") (class "Default")
      (node (ref "CHIP_6") (pin "P26") (pinfunction "R7_P26") (pintype "bidirectional"))
      (node (ref "D12") (pin "3") (pinfunction "RED_CATHODE_3") (pintype "bidirectional"))
    )
    (net (code "292") (name "Net-(CHIP_6-R8)") (class "Default")
      (node (ref "CHIP_6") (pin "P52") (pinfunction "R8_P52") (pintype "bidirectional"))
      (node (ref "D5") (pin "3") (pinfunction "RED_CATHODE_3") (pintype "bidirectional"))
    )
    (net (code "293") (name "Net-(CHIP_6-R9)") (class "Default")
      (node (ref "CHIP_6") (pin "P46") (pinfunction "R9_P46") (pintype "bidirectional"))
      (node (ref "D6") (pin "3") (pinfunction "RED_CATHODE_3") (pintype "bidirectional"))
    )
    (net (code "294") (name "Net-(CHIP_6-R10)") (class "Default")
      (node (ref "CHIP_6") (pin "P37") (pinfunction "R10_P37") (pintype "bidirectional"))
      (node (ref "D2") (pin "3") (pinfunction "RED_CATHODE_3") (pintype "bidirectional"))
    )
    (net (code "295") (name "Net-(CHIP_6-R11)") (class "Default")
      (node (ref "CHIP_6") (pin "P31") (pinfunction "R11_P31") (pintype "bidirectional"))
      (node (ref "D4") (pin "3") (pinfunction "RED_CATHODE_3") (pintype "bidirectional"))
    )
    (net (code "296") (name "Net-(CHIP_6-R12)") (class "Default")
      (node (ref "CHIP_6") (pin "P49") (pinfunction "R12_P49") (pintype "bidirectional"))
      (node (ref "D14") (pin "3") (pinfunction "RED_CATHODE_3") (pintype "bidirectional"))
    )
    (net (code "297") (name "Net-(CHIP_6-R13)") (class "Default")
      (node (ref "CHIP_6") (pin "P43") (pinfunction "R13_P43") (pintype "bidirectional"))
      (node (ref "D13") (pin "3") (pinfunction "RED_CATHODE_3") (pintype "bidirectional"))
    )
    (net (code "298") (name "Net-(CHIP_6-R14)") (class "Default")
      (node (ref "CHIP_6") (pin "P40") (pinfunction "R14_P40") (pintype "bidirectional"))
      (node (ref "D1") (pin "3") (pinfunction "RED_CATHODE_3") (pintype "bidirectional"))
    )
    (net (code "299") (name "Net-(CHIP_6-R15)") (class "Default")
      (node (ref "CHIP_6") (pin "P34") (pinfunction "R15_P34") (pintype "bidirectional"))
      (node (ref "D9") (pin "3") (pinfunction "RED_CATHODE_3") (pintype "bidirectional"))
    )
    (net (code "300") (name "VCC") (class "Default")
      (node (ref "C1") (pin "2") (pinfunction "2_2") (pintype "passive"))
      (node (ref "C2") (pin "2") (pinfunction "2_2") (pintype "passive"))
      (node (ref "C3") (pin "2") (pinfunction "2_2") (pintype "passive"))
      (node (ref "C4") (pin "2") (pinfunction "2_2") (pintype "passive"))
      (node (ref "C5") (pin "2") (pinfunction "2_2") (pintype "passive"))
      (node (ref "C6") (pin "2") (pinfunction "2_2") (pintype "passive"))
      (node (ref "CHIP_1") (pin "P54") (pinfunction "VCC_P54") (pintype "bidirectional"))
      (node (ref "CHIP_2") (pin "P54") (pinfunction "VCC_P54") (pintype "bidirectional"))
      (node (ref "CHIP_3") (pin "P54") (pinfunction "VCC_P54") (pintype "bidirectional"))
      (node (ref "CHIP_4") (pin "P54") (pinfunction "VCC_P54") (pintype "bidirectional"))
      (node (ref "CHIP_5") (pin "P54") (pinfunction "VCC_P54") (pintype "bidirectional"))
      (node (ref "CHIP_6") (pin "P54") (pinfunction "VCC_P54") (pintype "bidirectional"))
      (node (ref "D1") (pin "2") (pinfunction "CATHODE_2") (pintype "bidirectional"))
      (node (ref "D10") (pin "2") (pinfunction "CATHODE_2") (pintype "bidirectional"))
      (node (ref "D11") (pin "2") (pinfunction "CATHODE_2") (pintype "bidirectional"))
      (node (ref "D12") (pin "2") (pinfunction "CATHODE_2") (pintype "bidirectional"))
      (node (ref "D13") (pin "2") (pinfunction "CATHODE_2") (pintype "bidirectional"))
      (node (ref "D14") (pin "2") (pinfunction "CATHODE_2") (pintype "bidirectional"))
      (node (ref "D15") (pin "2") (pinfunction "CATHODE_2") (pintype "bidirectional"))
      (node (ref "D16") (pin "2") (pinfunction "CATHODE_2") (pintype "bidirectional"))
      (node (ref "D17") (pin "2") (pinfunction "CATHODE_2") (pintype "bidirectional"))
      (node (ref "D18") (pin "2") (pinfunction "CATHODE_2") (pintype "bidirectional"))
      (node (ref "D19") (pin "2") (pinfunction "CATHODE_2") (pintype "bidirectional"))
      (node (ref "D2") (pin "2") (pinfunction "CATHODE_2") (pintype "bidirectional"))
      (node (ref "D20") (pin "2") (pinfunction "CATHODE_2") (pintype "bidirectional"))
      (node (ref "D21") (pin "2") (pinfunction "CATHODE_2") (pintype "bidirectional"))
      (node (ref "D22") (pin "2") (pinfunction "CATHODE_2") (pintype "bidirectional"))
      (node (ref "D23") (pin "2") (pinfunction "CATHODE_2") (pintype "bidirectional"))
      (node (ref "D24") (pin "2") (pinfunction "CATHODE_2") (pintype "bidirectional"))
      (node (ref "D25") (pin "2") (pinfunction "CATHODE_2") (pintype "bidirectional"))
      (node (ref "D26") (pin "2") (pinfunction "CATHODE_2") (pintype "bidirectional"))
      (node (ref "D27") (pin "2") (pinfunction "CATHODE_2") (pintype "bidirectional"))
      (node (ref "D28") (pin "2") (pinfunction "CATHODE_2") (pintype "bidirectional"))
      (node (ref "D29") (pin "2") (pinfunction "CATHODE_2") (pintype "bidirectional"))
      (node (ref "D3") (pin "2") (pinfunction "CATHODE_2") (pintype "bidirectional"))
      (node (ref "D30") (pin "2") (pinfunction "CATHODE_2") (pintype "bidirectional"))
      (node (ref "D31") (pin "2") (pinfunction "CATHODE_2") (pintype "bidirectional"))
      (node (ref "D32") (pin "2") (pinfunction "CATHODE_2") (pintype "bidirectional"))
      (node (ref "D33") (pin "2") (pinfunction "CATHODE_2") (pintype "bidirectional"))
      (node (ref "D34") (pin "2") (pinfunction "CATHODE_2") (pintype "bidirectional"))
      (node (ref "D35") (pin "2") (pinfunction "CATHODE_2") (pintype "bidirectional"))
      (node (ref "D36") (pin "2") (pinfunction "CATHODE_2") (pintype "bidirectional"))
      (node (ref "D37") (pin "2") (pinfunction "CATHODE_2") (pintype "bidirectional"))
      (node (ref "D38") (pin "2") (pinfunction "CATHODE_2") (pintype "bidirectional"))
      (node (ref "D39") (pin "2") (pinfunction "CATHODE_2") (pintype "bidirectional"))
      (node (ref "D4") (pin "2") (pinfunction "CATHODE_2") (pintype "bidirectional"))
      (node (ref "D40") (pin "2") (pinfunction "CATHODE_2") (pintype "bidirectional"))
      (node (ref "D41") (pin "2") (pinfunction "CATHODE_2") (pintype "bidirectional"))
      (node (ref "D42") (pin "2") (pinfunction "CATHODE_2") (pintype "bidirectional"))
      (node (ref "D43") (pin "2") (pinfunction "CATHODE_2") (pintype "bidirectional"))
      (node (ref "D44") (pin "2") (pinfunction "CATHODE_2") (pintype "bidirectional"))
      (node (ref "D45") (pin "2") (pinfunction "CATHODE_2") (pintype "bidirectional"))
      (node (ref "D46") (pin "2") (pinfunction "CATHODE_2") (pintype "bidirectional"))
      (node (ref "D47") (pin "2") (pinfunction "CATHODE_2") (pintype "bidirectional"))
      (node (ref "D48") (pin "2") (pinfunction "CATHODE_2") (pintype "bidirectional"))
      (node (ref "D49") (pin "2") (pinfunction "CATHODE_2") (pintype "bidirectional"))
      (node (ref "D5") (pin "2") (pinfunction "CATHODE_2") (pintype "bidirectional"))
      (node (ref "D50") (pin "2") (pinfunction "CATHODE_2") (pintype "bidirectional"))
      (node (ref "D51") (pin "2") (pinfunction "CATHODE_2") (pintype "bidirectional"))
      (node (ref "D52") (pin "2") (pinfunction "CATHODE_2") (pintype "bidirectional"))
      (node (ref "D53") (pin "2") (pinfunction "CATHODE_2") (pintype "bidirectional"))
      (node (ref "D54") (pin "2") (pinfunction "CATHODE_2") (pintype "bidirectional"))
      (node (ref "D55") (pin "2") (pinfunction "CATHODE_2") (pintype "bidirectional"))
      (node (ref "D56") (pin "2") (pinfunction "CATHODE_2") (pintype "bidirectional"))
      (node (ref "D57") (pin "2") (pinfunction "CATHODE_2") (pintype "bidirectional"))
      (node (ref "D58") (pin "2") (pinfunction "CATHODE_2") (pintype "bidirectional"))
      (node (ref "D59") (pin "2") (pinfunction "CATHODE_2") (pintype "bidirectional"))
      (node (ref "D6") (pin "2") (pinfunction "CATHODE_2") (pintype "bidirectional"))
      (node (ref "D60") (pin "2") (pinfunction "CATHODE_2") (pintype "bidirectional"))
      (node (ref "D61") (pin "2") (pinfunction "CATHODE_2") (pintype "bidirectional"))
      (node (ref "D62") (pin "2") (pinfunction "CATHODE_2") (pintype "bidirectional"))
      (node (ref "D63") (pin "2") (pinfunction "CATHODE_2") (pintype "bidirectional"))
      (node (ref "D64") (pin "2") (pinfunction "CATHODE_2") (pintype "bidirectional"))
      (node (ref "D65") (pin "2") (pinfunction "CATHODE_2") (pintype "bidirectional"))
      (node (ref "D66") (pin "2") (pinfunction "CATHODE_2") (pintype "bidirectional"))
      (node (ref "D67") (pin "2") (pinfunction "CATHODE_2") (pintype "bidirectional"))
      (node (ref "D68") (pin "2") (pinfunction "CATHODE_2") (pintype "bidirectional"))
      (node (ref "D69") (pin "2") (pinfunction "CATHODE_2") (pintype "bidirectional"))
      (node (ref "D7") (pin "2") (pinfunction "CATHODE_2") (pintype "bidirectional"))
      (node (ref "D70") (pin "2") (pinfunction "CATHODE_2") (pintype "bidirectional"))
      (node (ref "D71") (pin "2") (pinfunction "CATHODE_2") (pintype "bidirectional"))
      (node (ref "D72") (pin "2") (pinfunction "CATHODE_2") (pintype "bidirectional"))
      (node (ref "D73") (pin "2") (pinfunction "CATHODE_2") (pintype "bidirectional"))
      (node (ref "D74") (pin "2") (pinfunction "CATHODE_2") (pintype "bidirectional"))
      (node (ref "D75") (pin "2") (pinfunction "CATHODE_2") (pintype "bidirectional"))
      (node (ref "D76") (pin "2") (pinfunction "CATHODE_2") (pintype "bidirectional"))
      (node (ref "D77") (pin "2") (pinfunction "CATHODE_2") (pintype "bidirectional"))
      (node (ref "D78") (pin "2") (pinfunction "CATHODE_2") (pintype "bidirectional"))
      (node (ref "D79") (pin "2") (pinfunction "CATHODE_2") (pintype "bidirectional"))
      (node (ref "D8") (pin "2") (pinfunction "CATHODE_2") (pintype "bidirectional"))
      (node (ref "D80") (pin "2") (pinfunction "CATHODE_2") (pintype "bidirectional"))
      (node (ref "D81") (pin "2") (pinfunction "CATHODE_2") (pintype "bidirectional"))
      (node (ref "D82") (pin "2") (pinfunction "CATHODE_2") (pintype "bidirectional"))
      (node (ref "D83") (pin "2") (pinfunction "CATHODE_2") (pintype "bidirectional"))
      (node (ref "D84") (pin "2") (pinfunction "CATHODE_2") (pintype "bidirectional"))
      (node (ref "D85") (pin "2") (pinfunction "CATHODE_2") (pintype "bidirectional"))
      (node (ref "D86") (pin "2") (pinfunction "CATHODE_2") (pintype "bidirectional"))
      (node (ref "D87") (pin "2") (pinfunction "CATHODE_2") (pintype "bidirectional"))
      (node (ref "D88") (pin "2") (pinfunction "CATHODE_2") (pintype "bidirectional"))
      (node (ref "D89") (pin "2") (pinfunction "CATHODE_2") (pintype "bidirectional"))
      (node (ref "D9") (pin "2") (pinfunction "CATHODE_2") (pintype "bidirectional"))
      (node (ref "D90") (pin "2") (pinfunction "CATHODE_2") (pintype "bidirectional"))
      (node (ref "D91") (pin "2") (pinfunction "CATHODE_2") (pintype "bidirectional"))
      (node (ref "D92") (pin "2") (pinfunction "CATHODE_2") (pintype "bidirectional"))
      (node (ref "D93") (pin "2") (pinfunction "CATHODE_2") (pintype "bidirectional"))
      (node (ref "D94") (pin "2") (pinfunction "CATHODE_2") (pintype "bidirectional"))
      (node (ref "D95") (pin "2") (pinfunction "CATHODE_2") (pintype "bidirectional"))
      (node (ref "D96") (pin "2") (pinfunction "CATHODE_2") (pintype "bidirectional"))
      (node (ref "U$1") (pin "P$2") (pinfunction "VCC_P$2") (pintype "bidirectional"))
    )
  )
)
